# TD8Edaughter.net
KiCad netlist of a schematic drawn in EAGLE
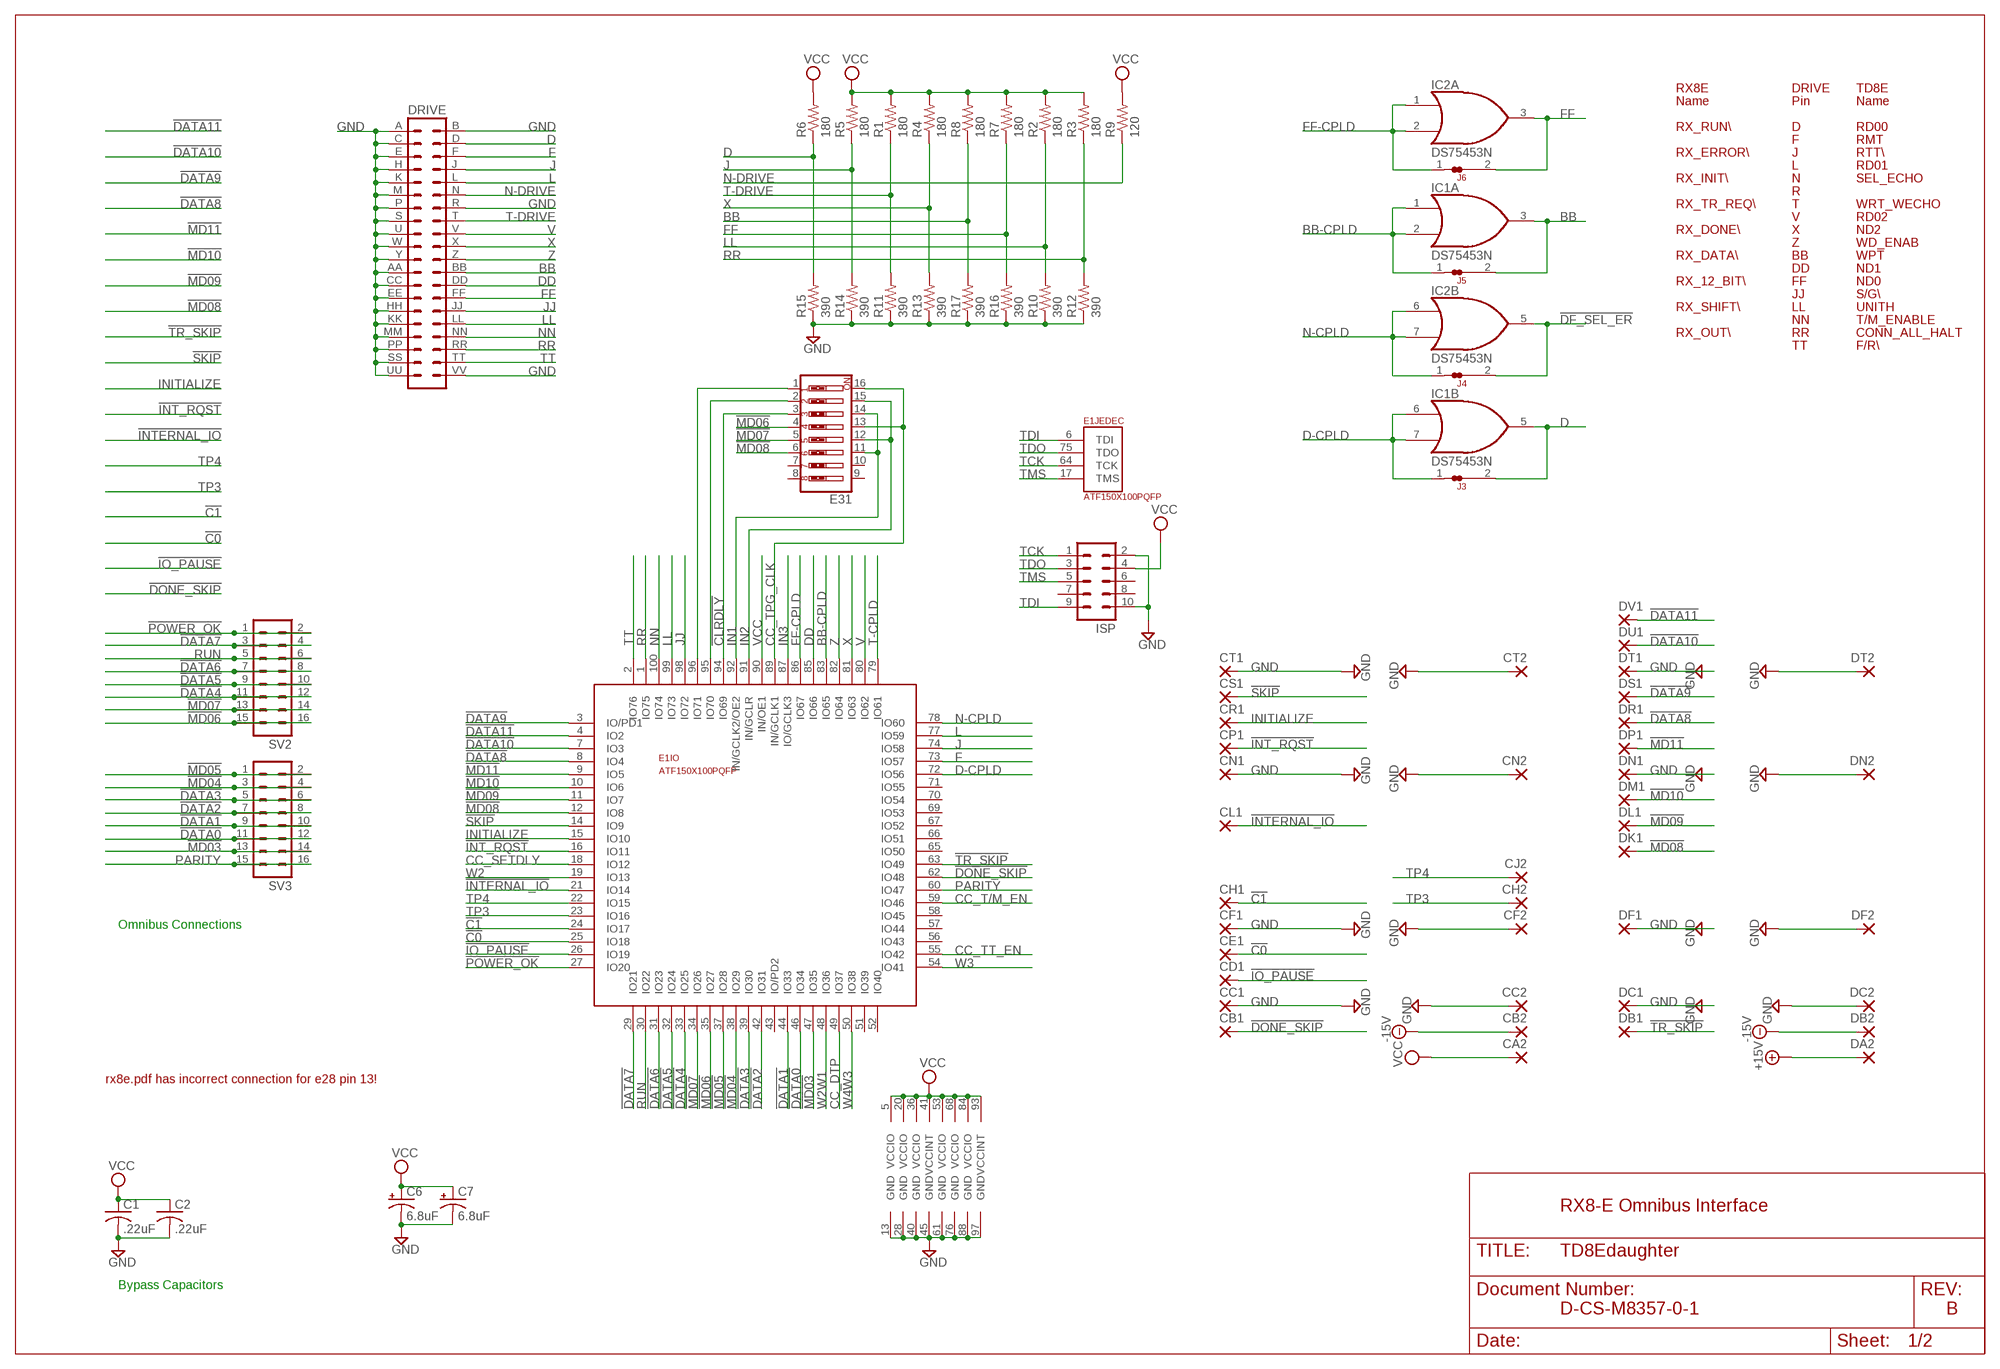
[diagram p0: schematic, sheet 1]
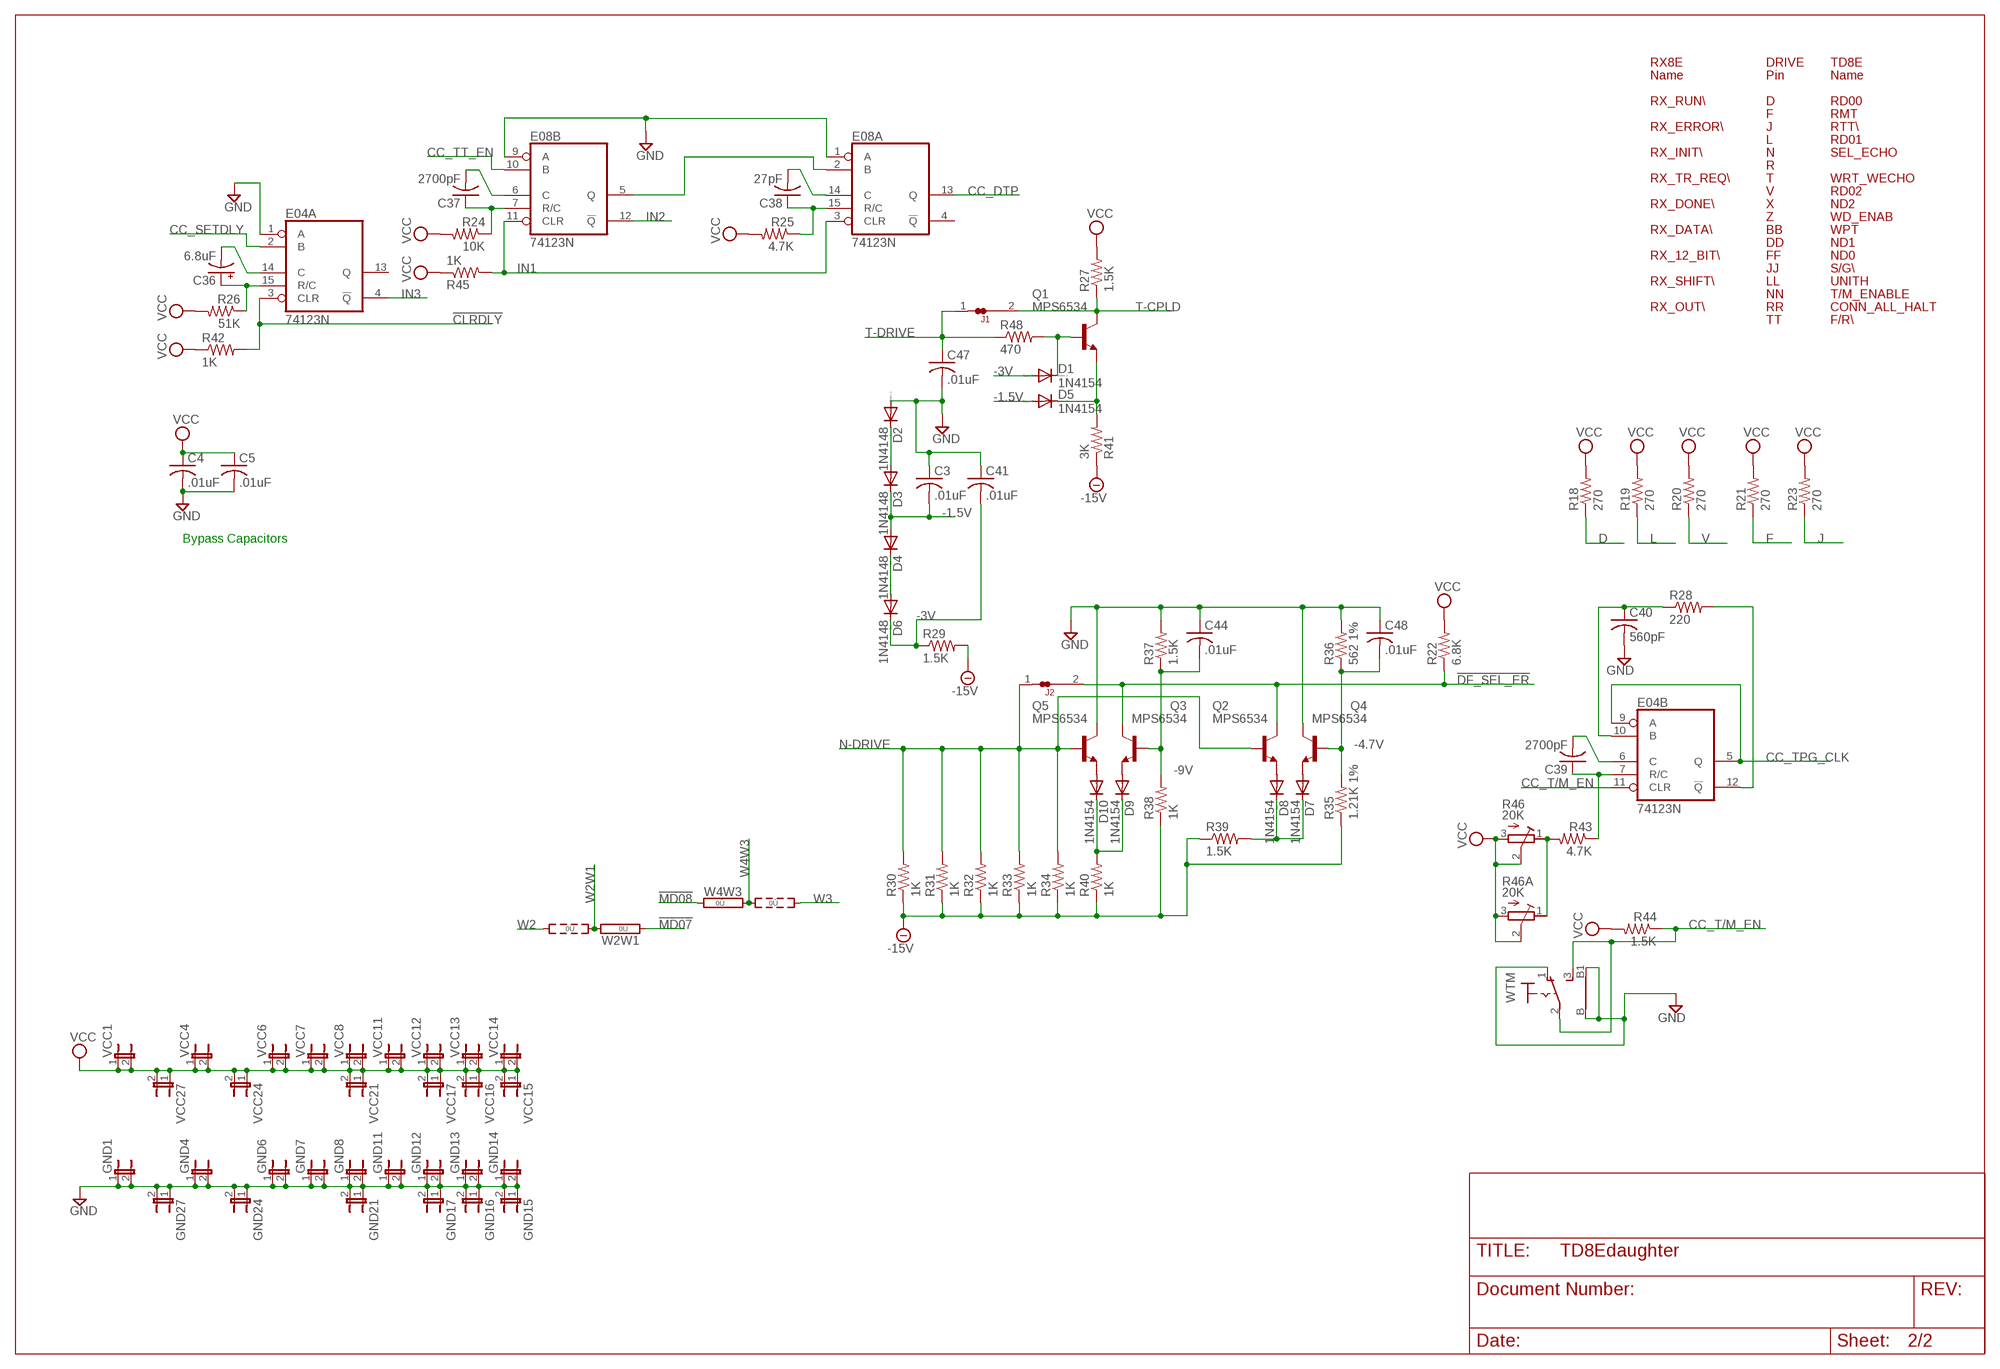
[diagram p1: schematic, sheet 2]

(export (version "E")
  (design (tool "Eeschema 10.0.6"))
  (components
    (comp (ref "C1")
      (value ".22uF")
      (footprint "eagle-import:C050-025X075")
      (libsource (lib "eagle-import") (part "C-US050-025X075"))
    )
    (comp (ref "C2")
      (value ".22uF")
      (footprint "eagle-import:C050-025X075")
      (libsource (lib "eagle-import") (part "C-US050-025X075"))
    )
    (comp (ref "C6")
      (value "6.8uF")
      (footprint "eagle-import:E12-8")
      (libsource (lib "eagle-import") (part "CPOL-USE20-8AXIAL"))
    )
    (comp (ref "C7")
      (value "6.8uF")
      (footprint "eagle-import:E12-8")
      (libsource (lib "eagle-import") (part "CPOL-USE20-8AXIAL"))
    )
    (comp (ref "CA2")
      (value "1,6/0,9")
      (footprint "eagle-import:1,6_0,9")
      (libsource (lib "eagle-import") (part "1,6/0,9"))
    )
    (comp (ref "CB1")
      (value "1,6/0,9")
      (footprint "eagle-import:1,6_0,9")
      (libsource (lib "eagle-import") (part "1,6/0,9"))
    )
    (comp (ref "CB2")
      (value "1,6/0,9")
      (footprint "eagle-import:1,6_0,9")
      (libsource (lib "eagle-import") (part "1,6/0,9"))
    )
    (comp (ref "CC1")
      (value "1,6/0,9")
      (footprint "eagle-import:1,6_0,9")
      (libsource (lib "eagle-import") (part "1,6/0,9"))
    )
    (comp (ref "CC2")
      (value "1,6/0,9")
      (footprint "eagle-import:1,6_0,9")
      (libsource (lib "eagle-import") (part "1,6/0,9"))
    )
    (comp (ref "CD1")
      (value "1,6/0,9")
      (footprint "eagle-import:1,6_0,9")
      (libsource (lib "eagle-import") (part "1,6/0,9"))
    )
    (comp (ref "CE1")
      (value "1,6/0,9")
      (footprint "eagle-import:1,6_0,9")
      (libsource (lib "eagle-import") (part "1,6/0,9"))
    )
    (comp (ref "CF1")
      (value "1,6/0,9")
      (footprint "eagle-import:1,6_0,9")
      (libsource (lib "eagle-import") (part "1,6/0,9"))
    )
    (comp (ref "CF2")
      (value "1,6/0,9")
      (footprint "eagle-import:1,6_0,9")
      (libsource (lib "eagle-import") (part "1,6/0,9"))
    )
    (comp (ref "CH1")
      (value "1,6/0,9")
      (footprint "eagle-import:1,6_0,9")
      (libsource (lib "eagle-import") (part "1,6/0,9"))
    )
    (comp (ref "CH2")
      (value "1,6/0,9")
      (footprint "eagle-import:1,6_0,9")
      (libsource (lib "eagle-import") (part "1,6/0,9"))
    )
    (comp (ref "CJ2")
      (value "1,6/0,9")
      (footprint "eagle-import:1,6_0,9")
      (libsource (lib "eagle-import") (part "1,6/0,9"))
    )
    (comp (ref "CL1")
      (value "1,6/0,9")
      (footprint "eagle-import:1,6_0,9")
      (libsource (lib "eagle-import") (part "1,6/0,9"))
    )
    (comp (ref "CN1")
      (value "1,6/0,9")
      (footprint "eagle-import:1,6_0,9")
      (libsource (lib "eagle-import") (part "1,6/0,9"))
    )
    (comp (ref "CN2")
      (value "1,6/0,9")
      (footprint "eagle-import:1,6_0,9")
      (libsource (lib "eagle-import") (part "1,6/0,9"))
    )
    (comp (ref "CP1")
      (value "1,6/0,9")
      (footprint "eagle-import:1,6_0,9")
      (libsource (lib "eagle-import") (part "1,6/0,9"))
    )
    (comp (ref "CR1")
      (value "1,6/0,9")
      (footprint "eagle-import:1,6_0,9")
      (libsource (lib "eagle-import") (part "1,6/0,9"))
    )
    (comp (ref "CS1")
      (value "1,6/0,9")
      (footprint "eagle-import:1,6_0,9")
      (libsource (lib "eagle-import") (part "1,6/0,9"))
    )
    (comp (ref "CT1")
      (value "1,6/0,9")
      (footprint "eagle-import:1,6_0,9")
      (libsource (lib "eagle-import") (part "1,6/0,9"))
    )
    (comp (ref "CT2")
      (value "1,6/0,9")
      (footprint "eagle-import:1,6_0,9")
      (libsource (lib "eagle-import") (part "1,6/0,9"))
    )
    (comp (ref "DA2")
      (value "1,6/0,9")
      (footprint "eagle-import:1,6_0,9")
      (libsource (lib "eagle-import") (part "1,6/0,9"))
    )
    (comp (ref "DB1")
      (value "1,6/0,9")
      (footprint "eagle-import:1,6_0,9")
      (libsource (lib "eagle-import") (part "1,6/0,9"))
    )
    (comp (ref "DB2")
      (value "1,6/0,9")
      (footprint "eagle-import:1,6_0,9")
      (libsource (lib "eagle-import") (part "1,6/0,9"))
    )
    (comp (ref "DC1")
      (value "1,6/0,9")
      (footprint "eagle-import:1,6_0,9")
      (libsource (lib "eagle-import") (part "1,6/0,9"))
    )
    (comp (ref "DC2")
      (value "1,6/0,9")
      (footprint "eagle-import:1,6_0,9")
      (libsource (lib "eagle-import") (part "1,6/0,9"))
    )
    (comp (ref "DF1")
      (value "1,6/0,9")
      (footprint "eagle-import:1,6_0,9")
      (libsource (lib "eagle-import") (part "1,6/0,9"))
    )
    (comp (ref "DF2")
      (value "1,6/0,9")
      (footprint "eagle-import:1,6_0,9")
      (libsource (lib "eagle-import") (part "1,6/0,9"))
    )
    (comp (ref "DK1")
      (value "1,6/0,9")
      (footprint "eagle-import:1,6_0,9")
      (libsource (lib "eagle-import") (part "1,6/0,9"))
    )
    (comp (ref "DL1")
      (value "1,6/0,9")
      (footprint "eagle-import:1,6_0,9")
      (libsource (lib "eagle-import") (part "1,6/0,9"))
    )
    (comp (ref "DM1")
      (value "1,6/0,9")
      (footprint "eagle-import:1,6_0,9")
      (libsource (lib "eagle-import") (part "1,6/0,9"))
    )
    (comp (ref "DN1")
      (value "1,6/0,9")
      (footprint "eagle-import:1,6_0,9")
      (libsource (lib "eagle-import") (part "1,6/0,9"))
    )
    (comp (ref "DN2")
      (value "1,6/0,9")
      (footprint "eagle-import:1,6_0,9")
      (libsource (lib "eagle-import") (part "1,6/0,9"))
    )
    (comp (ref "DP1")
      (value "1,6/0,9")
      (footprint "eagle-import:1,6_0,9")
      (libsource (lib "eagle-import") (part "1,6/0,9"))
    )
    (comp (ref "DR1")
      (value "1,6/0,9")
      (footprint "eagle-import:1,6_0,9")
      (libsource (lib "eagle-import") (part "1,6/0,9"))
    )
    (comp (ref "DRIVE")
      (value "DEC40PINH")
      (footprint "eagle-import:DEC40PINH")
      (libsource (lib "eagle-import") (part "DEC40PINH"))
    )
    (comp (ref "DS1")
      (value "1,6/0,9")
      (footprint "eagle-import:1,6_0,9")
      (libsource (lib "eagle-import") (part "1,6/0,9"))
    )
    (comp (ref "DT1")
      (value "1,6/0,9")
      (footprint "eagle-import:1,6_0,9")
      (libsource (lib "eagle-import") (part "1,6/0,9"))
    )
    (comp (ref "DT2")
      (value "1,6/0,9")
      (footprint "eagle-import:1,6_0,9")
      (libsource (lib "eagle-import") (part "1,6/0,9"))
    )
    (comp (ref "DU1")
      (value "1,6/0,9")
      (footprint "eagle-import:1,6_0,9")
      (libsource (lib "eagle-import") (part "1,6/0,9"))
    )
    (comp (ref "DV1")
      (value "1,6/0,9")
      (footprint "eagle-import:1,6_0,9")
      (libsource (lib "eagle-import") (part "1,6/0,9"))
    )
    (comp (ref "E1")
      (value "ATF150X100PQFP")
      (footprint "eagle-import:PQFP-100")
      (libsource (lib "eagle-import") (part "ATF150X100PQFP"))
    )
    (comp (ref "E31")
      (value "SW_DIP-8")
      (footprint "eagle-import:EDG-08")
      (libsource (lib "eagle-import") (part "SW_DIP-8"))
    )
    (comp (ref "IC1")
      (value "DS75453N")
      (footprint "eagle-import:DIL08")
      (libsource (lib "eagle-import") (part "DS75453N"))
    )
    (comp (ref "IC2")
      (value "DS75453N")
      (footprint "eagle-import:DIL08")
      (libsource (lib "eagle-import") (part "DS75453N"))
    )
    (comp (ref "ISP")
      (value "ML10")
      (footprint "eagle-import:ML10")
      (libsource (lib "eagle-import") (part "ML10"))
    )
    (comp (ref "J3")
      (value "JUMPER-NC2")
      (footprint "eagle-import:NC2")
      (libsource (lib "eagle-import") (part "JUMPER-NC2"))
    )
    (comp (ref "J4")
      (value "JUMPER-NC2")
      (footprint "eagle-import:NC2")
      (libsource (lib "eagle-import") (part "JUMPER-NC2"))
    )
    (comp (ref "J5")
      (value "JUMPER-NC2")
      (footprint "eagle-import:NC2")
      (libsource (lib "eagle-import") (part "JUMPER-NC2"))
    )
    (comp (ref "J6")
      (value "JUMPER-NC2")
      (footprint "eagle-import:NC2")
      (libsource (lib "eagle-import") (part "JUMPER-NC2"))
    )
    (comp (ref "R1")
      (value "180")
      (footprint "eagle-import:0207_10")
      (libsource (lib "eagle-import") (part "R-US_0207/10"))
    )
    (comp (ref "R2")
      (value "180")
      (footprint "eagle-import:0207_10")
      (libsource (lib "eagle-import") (part "R-US_0207/10"))
    )
    (comp (ref "R3")
      (value "180")
      (footprint "eagle-import:0207_10")
      (libsource (lib "eagle-import") (part "R-US_0207/10"))
    )
    (comp (ref "R4")
      (value "180")
      (footprint "eagle-import:0207_10")
      (libsource (lib "eagle-import") (part "R-US_0207/10"))
    )
    (comp (ref "R5")
      (value "180")
      (footprint "eagle-import:0207_10")
      (libsource (lib "eagle-import") (part "R-US_0207/10"))
    )
    (comp (ref "R6")
      (value "180")
      (footprint "eagle-import:0207_10")
      (libsource (lib "eagle-import") (part "R-US_0207/10"))
    )
    (comp (ref "R7")
      (value "180")
      (footprint "eagle-import:0207_10")
      (libsource (lib "eagle-import") (part "R-US_0207/10"))
    )
    (comp (ref "R8")
      (value "180")
      (footprint "eagle-import:0207_10")
      (libsource (lib "eagle-import") (part "R-US_0207/10"))
    )
    (comp (ref "R9")
      (value "120")
      (footprint "eagle-import:0207_10")
      (libsource (lib "eagle-import") (part "R-US_0207/10"))
    )
    (comp (ref "R10")
      (value "390")
      (footprint "eagle-import:0207_10")
      (libsource (lib "eagle-import") (part "R-US_0207/10"))
    )
    (comp (ref "R11")
      (value "390")
      (footprint "eagle-import:0207_10")
      (libsource (lib "eagle-import") (part "R-US_0207/10"))
    )
    (comp (ref "R12")
      (value "390")
      (footprint "eagle-import:0207_10")
      (libsource (lib "eagle-import") (part "R-US_0207/10"))
    )
    (comp (ref "R13")
      (value "390")
      (footprint "eagle-import:0207_10")
      (libsource (lib "eagle-import") (part "R-US_0207/10"))
    )
    (comp (ref "R14")
      (value "390")
      (footprint "eagle-import:0207_10")
      (libsource (lib "eagle-import") (part "R-US_0207/10"))
    )
    (comp (ref "R15")
      (value "390")
      (footprint "eagle-import:0207_10")
      (libsource (lib "eagle-import") (part "R-US_0207/10"))
    )
    (comp (ref "R16")
      (value "390")
      (footprint "eagle-import:0207_10")
      (libsource (lib "eagle-import") (part "R-US_0207/10"))
    )
    (comp (ref "R17")
      (value "390")
      (footprint "eagle-import:0207_10")
      (libsource (lib "eagle-import") (part "R-US_0207/10"))
    )
    (comp (ref "SV2")
      (value "MA08-2")
      (footprint "eagle-import:MA08-2")
      (libsource (lib "eagle-import") (part "MA08-2"))
    )
    (comp (ref "SV3")
      (value "MA08-2")
      (footprint "eagle-import:MA08-2")
      (libsource (lib "eagle-import") (part "MA08-2"))
    )
    (comp (ref "C3")
      (value ".01uF")
      (footprint "eagle-import:C050-025X075")
      (libsource (lib "eagle-import") (part "C-US050-025X075"))
    )
    (comp (ref "C4")
      (value ".01uF")
      (footprint "eagle-import:C050-025X075")
      (libsource (lib "eagle-import") (part "C-US050-025X075"))
    )
    (comp (ref "C5")
      (value ".01uF")
      (footprint "eagle-import:C050-025X075")
      (libsource (lib "eagle-import") (part "C-US050-025X075"))
    )
    (comp (ref "C36")
      (value "6.8uF")
      (footprint "eagle-import:E12-8")
      (libsource (lib "eagle-import") (part "CPOL-USE20-8AXIAL"))
    )
    (comp (ref "C37")
      (value "2700pF")
      (footprint "eagle-import:C102-043X133")
      (libsource (lib "eagle-import") (part "C-US102-043X133"))
    )
    (comp (ref "C38")
      (value "27pF")
      (footprint "eagle-import:C050-025X075")
      (libsource (lib "eagle-import") (part "C-US050-025X075"))
    )
    (comp (ref "C39")
      (value "2700pF")
      (footprint "eagle-import:C102-043X133")
      (libsource (lib "eagle-import") (part "C-US102-043X133"))
    )
    (comp (ref "C40")
      (value "560pF")
      (footprint "eagle-import:C075-032X103")
      (libsource (lib "eagle-import") (part "C-US075-032X103"))
    )
    (comp (ref "C41")
      (value ".01uF")
      (footprint "eagle-import:C050-025X075")
      (libsource (lib "eagle-import") (part "C-US050-025X075"))
    )
    (comp (ref "C44")
      (value ".01uF")
      (footprint "eagle-import:C050-025X075")
      (libsource (lib "eagle-import") (part "C-US050-025X075"))
    )
    (comp (ref "C47")
      (value ".01uF")
      (footprint "eagle-import:C050-025X075")
      (libsource (lib "eagle-import") (part "C-US050-025X075"))
    )
    (comp (ref "C48")
      (value ".01uF")
      (footprint "eagle-import:C050-025X075")
      (libsource (lib "eagle-import") (part "C-US050-025X075"))
    )
    (comp (ref "D1")
      (value "1N4154")
      (footprint "eagle-import:DO35-10")
      (libsource (lib "eagle-import") (part "1N4148DO35-10"))
    )
    (comp (ref "D2")
      (value "1N4148")
      (footprint "eagle-import:DO35-10")
      (libsource (lib "eagle-import") (part "1N4148DO35-10"))
    )
    (comp (ref "D3")
      (value "1N4148")
      (footprint "eagle-import:DO35-10")
      (libsource (lib "eagle-import") (part "1N4148DO35-10"))
    )
    (comp (ref "D4")
      (value "1N4148")
      (footprint "eagle-import:DO35-10")
      (libsource (lib "eagle-import") (part "1N4148DO35-10"))
    )
    (comp (ref "D5")
      (value "1N4154")
      (footprint "eagle-import:DO35-10")
      (libsource (lib "eagle-import") (part "1N4148DO35-10"))
    )
    (comp (ref "D6")
      (value "1N4148")
      (footprint "eagle-import:DO35-10")
      (libsource (lib "eagle-import") (part "1N4148DO35-10"))
    )
    (comp (ref "D7")
      (value "1N4154")
      (footprint "eagle-import:DO35-10")
      (libsource (lib "eagle-import") (part "1N4148DO35-10"))
    )
    (comp (ref "D8")
      (value "1N4154")
      (footprint "eagle-import:DO35-10")
      (libsource (lib "eagle-import") (part "1N4148DO35-10"))
    )
    (comp (ref "D9")
      (value "1N4154")
      (footprint "eagle-import:DO35-10")
      (libsource (lib "eagle-import") (part "1N4148DO35-10"))
    )
    (comp (ref "D10")
      (value "1N4154")
      (footprint "eagle-import:DO35-10")
      (libsource (lib "eagle-import") (part "1N4148DO35-10"))
    )
    (comp (ref "E04")
      (value "74123N")
      (footprint "eagle-import:DIL16")
      (libsource (lib "eagle-import") (part "74123N"))
    )
    (comp (ref "E08")
      (value "74123N")
      (footprint "eagle-import:DIL16")
      (libsource (lib "eagle-import") (part "74123N"))
    )
    (comp (ref "GND1")
      (value "JP1E")
      (footprint "eagle-import:JP1")
      (libsource (lib "eagle-import") (part "JP1E"))
    )
    (comp (ref "GND4")
      (value "JP1E")
      (footprint "eagle-import:JP1")
      (libsource (lib "eagle-import") (part "JP1E"))
    )
    (comp (ref "GND6")
      (value "JP1E")
      (footprint "eagle-import:JP1")
      (libsource (lib "eagle-import") (part "JP1E"))
    )
    (comp (ref "GND7")
      (value "JP1E")
      (footprint "eagle-import:JP1")
      (libsource (lib "eagle-import") (part "JP1E"))
    )
    (comp (ref "GND8")
      (value "JP1E")
      (footprint "eagle-import:JP1")
      (libsource (lib "eagle-import") (part "JP1E"))
    )
    (comp (ref "GND11")
      (value "JP1E")
      (footprint "eagle-import:JP1")
      (libsource (lib "eagle-import") (part "JP1E"))
    )
    (comp (ref "GND12")
      (value "JP1E")
      (footprint "eagle-import:JP1")
      (libsource (lib "eagle-import") (part "JP1E"))
    )
    (comp (ref "GND13")
      (value "JP1E")
      (footprint "eagle-import:JP1")
      (libsource (lib "eagle-import") (part "JP1E"))
    )
    (comp (ref "GND14")
      (value "JP1E")
      (footprint "eagle-import:JP1")
      (libsource (lib "eagle-import") (part "JP1E"))
    )
    (comp (ref "GND15")
      (value "JP1E")
      (footprint "eagle-import:JP1")
      (libsource (lib "eagle-import") (part "JP1E"))
    )
    (comp (ref "GND16")
      (value "JP1E")
      (footprint "eagle-import:JP1")
      (libsource (lib "eagle-import") (part "JP1E"))
    )
    (comp (ref "GND17")
      (value "JP1E")
      (footprint "eagle-import:JP1")
      (libsource (lib "eagle-import") (part "JP1E"))
    )
    (comp (ref "GND21")
      (value "JP1E")
      (footprint "eagle-import:JP1")
      (libsource (lib "eagle-import") (part "JP1E"))
    )
    (comp (ref "GND24")
      (value "JP1E")
      (footprint "eagle-import:JP1")
      (libsource (lib "eagle-import") (part "JP1E"))
    )
    (comp (ref "GND27")
      (value "JP1E")
      (footprint "eagle-import:JP1")
      (libsource (lib "eagle-import") (part "JP1E"))
    )
    (comp (ref "J1")
      (value "JUMPER-NC")
      (footprint "eagle-import:NC1")
      (libsource (lib "eagle-import") (part "JUMPER-NC1"))
    )
    (comp (ref "J2")
      (value "JUMPER-NC")
      (footprint "eagle-import:NC1")
      (libsource (lib "eagle-import") (part "JUMPER-NC1"))
    )
    (comp (ref "Q1")
      (value "MPS6534")
      (footprint "eagle-import:TO5")
      (libsource (lib "eagle-import") (part "2N2219"))
    )
    (comp (ref "Q2")
      (value "MPS6534")
      (footprint "eagle-import:TO5")
      (libsource (lib "eagle-import") (part "2N2219"))
    )
    (comp (ref "Q3")
      (value "MPS6534")
      (footprint "eagle-import:TO5")
      (libsource (lib "eagle-import") (part "2N2219"))
    )
    (comp (ref "Q4")
      (value "MPS6534")
      (footprint "eagle-import:TO5")
      (libsource (lib "eagle-import") (part "2N2219"))
    )
    (comp (ref "Q5")
      (value "MPS6534")
      (footprint "eagle-import:TO5")
      (libsource (lib "eagle-import") (part "2N2219"))
    )
    (comp (ref "R18")
      (value "270")
      (footprint "eagle-import:0207_10")
      (libsource (lib "eagle-import") (part "R-US_0207/10"))
    )
    (comp (ref "R19")
      (value "270")
      (footprint "eagle-import:0207_10")
      (libsource (lib "eagle-import") (part "R-US_0207/10"))
    )
    (comp (ref "R20")
      (value "270")
      (footprint "eagle-import:0207_10")
      (libsource (lib "eagle-import") (part "R-US_0207/10"))
    )
    (comp (ref "R21")
      (value "270")
      (footprint "eagle-import:0207_10")
      (libsource (lib "eagle-import") (part "R-US_0207/10"))
    )
    (comp (ref "R22")
      (value "6.8K")
      (footprint "eagle-import:0207_10")
      (libsource (lib "eagle-import") (part "R-US_0207/10"))
    )
    (comp (ref "R23")
      (value "270")
      (footprint "eagle-import:0207_10")
      (libsource (lib "eagle-import") (part "R-US_0207/10"))
    )
    (comp (ref "R24")
      (value "10K")
      (footprint "eagle-import:0207_10")
      (libsource (lib "eagle-import") (part "R-US_0207/10"))
    )
    (comp (ref "R25")
      (value "4.7K")
      (footprint "eagle-import:0207_10")
      (libsource (lib "eagle-import") (part "R-US_0207/10"))
    )
    (comp (ref "R26")
      (value "51K")
      (footprint "eagle-import:0207_10")
      (libsource (lib "eagle-import") (part "R-US_0207/10"))
    )
    (comp (ref "R27")
      (value "1.5K")
      (footprint "eagle-import:0207_10")
      (libsource (lib "eagle-import") (part "R-US_0207/10"))
    )
    (comp (ref "R28")
      (value "220")
      (footprint "eagle-import:0207_10")
      (libsource (lib "eagle-import") (part "R-US_0207/10"))
    )
    (comp (ref "R29")
      (value "1.5K")
      (footprint "eagle-import:0207_10")
      (libsource (lib "eagle-import") (part "R-US_0207/10"))
    )
    (comp (ref "R30")
      (value "1K")
      (footprint "eagle-import:0207_10")
      (libsource (lib "eagle-import") (part "R-US_0207/10"))
    )
    (comp (ref "R31")
      (value "1K")
      (footprint "eagle-import:0207_10")
      (libsource (lib "eagle-import") (part "R-US_0207/10"))
    )
    (comp (ref "R32")
      (value "1K")
      (footprint "eagle-import:0207_10")
      (libsource (lib "eagle-import") (part "R-US_0207/10"))
    )
    (comp (ref "R33")
      (value "1K")
      (footprint "eagle-import:0207_10")
      (libsource (lib "eagle-import") (part "R-US_0207/10"))
    )
    (comp (ref "R34")
      (value "1K")
      (footprint "eagle-import:0207_10")
      (libsource (lib "eagle-import") (part "R-US_0207/10"))
    )
    (comp (ref "R35")
      (value "1.21K 1%")
      (footprint "eagle-import:0207_15")
      (libsource (lib "eagle-import") (part "R-US_0207/15"))
    )
    (comp (ref "R36")
      (value "562 1%")
      (footprint "eagle-import:0207_15")
      (libsource (lib "eagle-import") (part "R-US_0207/15"))
    )
    (comp (ref "R37")
      (value "1.5K")
      (footprint "eagle-import:0207_10")
      (libsource (lib "eagle-import") (part "R-US_0207/10"))
    )
    (comp (ref "R38")
      (value "1K")
      (footprint "eagle-import:0207_10")
      (libsource (lib "eagle-import") (part "R-US_0207/10"))
    )
    (comp (ref "R39")
      (value "1.5K")
      (footprint "eagle-import:0207_10")
      (libsource (lib "eagle-import") (part "R-US_0207/10"))
    )
    (comp (ref "R40")
      (value "1K")
      (footprint "eagle-import:0207_10")
      (libsource (lib "eagle-import") (part "R-US_0207/10"))
    )
    (comp (ref "R41")
      (value "3K")
      (footprint "eagle-import:0207_10")
      (libsource (lib "eagle-import") (part "R-US_0207/10"))
    )
    (comp (ref "R42")
      (value "1K")
      (footprint "eagle-import:0207_10")
      (libsource (lib "eagle-import") (part "R-US_0207/10"))
    )
    (comp (ref "R43")
      (value "4.7K")
      (footprint "eagle-import:0207_10")
      (libsource (lib "eagle-import") (part "R-US_0207/10"))
    )
    (comp (ref "R44")
      (value "1.5K")
      (footprint "eagle-import:0207_10")
      (libsource (lib "eagle-import") (part "R-US_0207/10"))
    )
    (comp (ref "R45")
      (value "1K")
      (footprint "eagle-import:0207_10")
      (libsource (lib "eagle-import") (part "R-US_0207/10"))
    )
    (comp (ref "R46")
      (value "20K")
      (footprint "eagle-import:3006Y")
      (libsource (lib "eagle-import") (part "275P"))
    )
    (comp (ref "R46A")
      (value "20K")
      (footprint "eagle-import:RTRIM3006P")
      (libsource (lib "eagle-import") (part "R-TRIMM3006P"))
    )
    (comp (ref "R48")
      (value "470")
      (footprint "eagle-import:0207_10")
      (libsource (lib "eagle-import") (part "R-US_0207/10"))
    )
    (comp (ref "VCC1")
      (value "JP1E")
      (footprint "eagle-import:JP1")
      (libsource (lib "eagle-import") (part "JP1E"))
    )
    (comp (ref "VCC4")
      (value "JP1E")
      (footprint "eagle-import:JP1")
      (libsource (lib "eagle-import") (part "JP1E"))
    )
    (comp (ref "VCC6")
      (value "JP1E")
      (footprint "eagle-import:JP1")
      (libsource (lib "eagle-import") (part "JP1E"))
    )
    (comp (ref "VCC7")
      (value "JP1E")
      (footprint "eagle-import:JP1")
      (libsource (lib "eagle-import") (part "JP1E"))
    )
    (comp (ref "VCC8")
      (value "JP1E")
      (footprint "eagle-import:JP1")
      (libsource (lib "eagle-import") (part "JP1E"))
    )
    (comp (ref "VCC11")
      (value "JP1E")
      (footprint "eagle-import:JP1")
      (libsource (lib "eagle-import") (part "JP1E"))
    )
    (comp (ref "VCC12")
      (value "JP1E")
      (footprint "eagle-import:JP1")
      (libsource (lib "eagle-import") (part "JP1E"))
    )
    (comp (ref "VCC13")
      (value "JP1E")
      (footprint "eagle-import:JP1")
      (libsource (lib "eagle-import") (part "JP1E"))
    )
    (comp (ref "VCC14")
      (value "JP1E")
      (footprint "eagle-import:JP1")
      (libsource (lib "eagle-import") (part "JP1E"))
    )
    (comp (ref "VCC15")
      (value "JP1E")
      (footprint "eagle-import:JP1")
      (libsource (lib "eagle-import") (part "JP1E"))
    )
    (comp (ref "VCC16")
      (value "JP1E")
      (footprint "eagle-import:JP1")
      (libsource (lib "eagle-import") (part "JP1E"))
    )
    (comp (ref "VCC17")
      (value "JP1E")
      (footprint "eagle-import:JP1")
      (libsource (lib "eagle-import") (part "JP1E"))
    )
    (comp (ref "VCC21")
      (value "JP1E")
      (footprint "eagle-import:JP1")
      (libsource (lib "eagle-import") (part "JP1E"))
    )
    (comp (ref "VCC24")
      (value "JP1E")
      (footprint "eagle-import:JP1")
      (libsource (lib "eagle-import") (part "JP1E"))
    )
    (comp (ref "VCC27")
      (value "JP1E")
      (footprint "eagle-import:JP1")
      (libsource (lib "eagle-import") (part "JP1E"))
    )
    (comp (ref "W2W1")
      (value "0R2")
      (footprint "eagle-import:0R2_10")
      (libsource (lib "eagle-import") (part "0R2"))
    )
    (comp (ref "W4W3")
      (value "0R2")
      (footprint "eagle-import:0R2_10")
      (libsource (lib "eagle-import") (part "0R2"))
    )
    (comp (ref "WTM")
      (value "9070-1W")
      (footprint "eagle-import:9070-1W")
      (libsource (lib "eagle-import") (part "9070-1W"))
    )
  )
  (nets
    (net (code "1") (name "+15V") (class "Default")
      (node (ref "DA2") (pin "1") (pinfunction "P_1") (pintype "passive"))
    )
    (net (code "2") (name "-1.5V") (class "Default")
      (node (ref "C3") (pin "2") (pinfunction "2_2") (pintype "passive"))
      (node (ref "D3") (pin "C") (pinfunction "C_C") (pintype "passive"))
      (node (ref "D4") (pin "A") (pinfunction "A_A") (pintype "passive"))
      (node (ref "D5") (pin "A") (pinfunction "A_A") (pintype "passive"))
    )
    (net (code "3") (name "-3V") (class "Default")
      (node (ref "C41") (pin "2") (pinfunction "2_2") (pintype "passive"))
      (node (ref "D1") (pin "A") (pinfunction "A_A") (pintype "passive"))
      (node (ref "D6") (pin "C") (pinfunction "C_C") (pintype "passive"))
      (node (ref "R29") (pin "1") (pinfunction "1_1") (pintype "passive"))
    )
    (net (code "4") (name "-4.7V") (class "Default")
      (node (ref "C48") (pin "2") (pinfunction "2_2") (pintype "passive"))
      (node (ref "Q4") (pin "2") (pinfunction "B_2") (pintype "passive"))
      (node (ref "R35") (pin "2") (pinfunction "2_2") (pintype "passive"))
      (node (ref "R36") (pin "1") (pinfunction "1_1") (pintype "passive"))
    )
    (net (code "5") (name "-9V") (class "Default")
      (node (ref "C44") (pin "2") (pinfunction "2_2") (pintype "passive"))
      (node (ref "Q3") (pin "2") (pinfunction "B_2") (pintype "passive"))
      (node (ref "R37") (pin "1") (pinfunction "1_1") (pintype "passive"))
      (node (ref "R38") (pin "2") (pinfunction "2_2") (pintype "passive"))
    )
    (net (code "6") (name "-15V") (class "Default")
      (node (ref "CB2") (pin "1") (pinfunction "P_1") (pintype "passive"))
      (node (ref "DB2") (pin "1") (pinfunction "P_1") (pintype "passive"))
      (node (ref "R29") (pin "2") (pinfunction "2_2") (pintype "passive"))
      (node (ref "R30") (pin "1") (pinfunction "1_1") (pintype "passive"))
      (node (ref "R31") (pin "1") (pinfunction "1_1") (pintype "passive"))
      (node (ref "R32") (pin "1") (pinfunction "1_1") (pintype "passive"))
      (node (ref "R33") (pin "1") (pinfunction "1_1") (pintype "passive"))
      (node (ref "R34") (pin "1") (pinfunction "1_1") (pintype "passive"))
      (node (ref "R35") (pin "1") (pinfunction "1_1") (pintype "passive"))
      (node (ref "R38") (pin "1") (pinfunction "1_1") (pintype "passive"))
      (node (ref "R39") (pin "1") (pinfunction "1_1") (pintype "passive"))
      (node (ref "R40") (pin "1") (pinfunction "1_1") (pintype "passive"))
      (node (ref "R41") (pin "1") (pinfunction "1_1") (pintype "passive"))
    )
    (net (code "7") (name "BB") (class "Default")
      (node (ref "DRIVE") (pin "BB") (pinfunction "24_BB") (pintype "bidirectional"))
      (node (ref "IC1") (pin "3") (pinfunction "O_3") (pintype "open_collector"))
      (node (ref "J5") (pin "2") (pinfunction "2_2") (pintype "bidirectional"))
      (node (ref "R17") (pin "2") (pinfunction "2_2") (pintype "passive"))
      (node (ref "R8") (pin "1") (pinfunction "1_1") (pintype "passive"))
    )
    (net (code "8") (name "BB-CPLD") (class "Default")
      (node (ref "E1") (pin "83") (pinfunction "IO65_83") (pintype "bidirectional"))
      (node (ref "IC1") (pin "1") (pinfunction "I0_1") (pintype "input"))
      (node (ref "IC1") (pin "2") (pinfunction "I1_2") (pintype "input"))
      (node (ref "J5") (pin "1") (pinfunction "1_1") (pintype "bidirectional"))
    )
    (net (code "9") (name "CC_DTP") (class "Default")
      (node (ref "E08") (pin "13") (pinfunction "Q_13") (pintype "output"))
      (node (ref "E1") (pin "49") (pinfunction "IO37_49") (pintype "bidirectional"))
    )
    (net (code "10") (name "CC_SETDLY") (class "Default")
      (node (ref "E04") (pin "2") (pinfunction "B_2") (pintype "input"))
      (node (ref "E1") (pin "18") (pinfunction "IO12_18") (pintype "bidirectional"))
    )
    (net (code "11") (name "CC_TPG_CLK") (class "Default")
      (node (ref "E04") (pin "5") (pinfunction "Q_5") (pintype "output"))
      (node (ref "E04") (pin "9") (pinfunction "A_9") (pintype "input"))
      (node (ref "E1") (pin "89") (pinfunction "IN/GCLK1_89") (pintype "input"))
      (node (ref "E31") (pin "13") (pinfunction "13_13") (pintype "passive"))
      (node (ref "E31") (pin "16") (pinfunction "16_16") (pintype "passive"))
    )
    (net (code "12") (name "CC_TT_EN") (class "Default")
      (node (ref "E08") (pin "10") (pinfunction "B_10") (pintype "input"))
      (node (ref "E1") (pin "55") (pinfunction "IO42_55") (pintype "bidirectional"))
    )
    (net (code "13") (name "CC_T{slash}M_EN") (class "Default")
      (node (ref "E04") (pin "11") (pinfunction "CLR_11") (pintype "input"))
      (node (ref "E1") (pin "59") (pinfunction "IO46_59") (pintype "bidirectional"))
      (node (ref "R44") (pin "1") (pinfunction "1_1") (pintype "passive"))
      (node (ref "WTM") (pin "2") (pinfunction "P_2") (pintype "passive"))
      (node (ref "WTM") (pin "3") (pinfunction "S_3") (pintype "passive"))
    )
    (net (code "14") (name "D") (class "Default")
      (node (ref "DRIVE") (pin "D") (pinfunction "4_D") (pintype "bidirectional"))
      (node (ref "IC1") (pin "5") (pinfunction "O_5") (pintype "open_collector"))
      (node (ref "J3") (pin "2") (pinfunction "2_2") (pintype "bidirectional"))
      (node (ref "R15") (pin "2") (pinfunction "2_2") (pintype "passive"))
      (node (ref "R18") (pin "1") (pinfunction "1_1") (pintype "passive"))
      (node (ref "R6") (pin "1") (pinfunction "1_1") (pintype "passive"))
    )
    (net (code "15") (name "D-CPLD") (class "Default")
      (node (ref "E1") (pin "72") (pinfunction "IO56_72") (pintype "bidirectional"))
      (node (ref "IC1") (pin "6") (pinfunction "I0_6") (pintype "input"))
      (node (ref "IC1") (pin "7") (pinfunction "I1_7") (pintype "input"))
      (node (ref "J3") (pin "1") (pinfunction "1_1") (pintype "bidirectional"))
    )
    (net (code "16") (name "DD") (class "Default")
      (node (ref "DRIVE") (pin "DD") (pinfunction "26_DD") (pintype "bidirectional"))
      (node (ref "E1") (pin "85") (pinfunction "IO66_85") (pintype "bidirectional"))
    )
    (net (code "17") (name "F") (class "Default")
      (node (ref "DRIVE") (pin "F") (pinfunction "6_F") (pintype "bidirectional"))
      (node (ref "E1") (pin "73") (pinfunction "IO57_73") (pintype "bidirectional"))
      (node (ref "R21") (pin "1") (pinfunction "1_1") (pintype "passive"))
    )
    (net (code "18") (name "FF") (class "Default")
      (node (ref "DRIVE") (pin "FF") (pinfunction "28_FF") (pintype "bidirectional"))
      (node (ref "IC2") (pin "3") (pinfunction "O_3") (pintype "open_collector"))
      (node (ref "J6") (pin "2") (pinfunction "2_2") (pintype "bidirectional"))
      (node (ref "R16") (pin "2") (pinfunction "2_2") (pintype "passive"))
      (node (ref "R7") (pin "1") (pinfunction "1_1") (pintype "passive"))
    )
    (net (code "19") (name "FF-CPLD") (class "Default")
      (node (ref "E1") (pin "86") (pinfunction "IO67_86") (pintype "bidirectional"))
      (node (ref "IC2") (pin "1") (pinfunction "I0_1") (pintype "input"))
      (node (ref "IC2") (pin "2") (pinfunction "I1_2") (pintype "input"))
      (node (ref "J6") (pin "1") (pinfunction "1_1") (pintype "bidirectional"))
    )
    (net (code "20") (name "GND") (class "Default")
      (node (ref "C1") (pin "2") (pinfunction "2_2") (pintype "passive"))
      (node (ref "C2") (pin "2") (pinfunction "2_2") (pintype "passive"))
      (node (ref "C3") (pin "1") (pinfunction "1_1") (pintype "passive"))
      (node (ref "C4") (pin "2") (pinfunction "2_2") (pintype "passive"))
      (node (ref "C40") (pin "2") (pinfunction "2_2") (pintype "passive"))
      (node (ref "C41") (pin "1") (pinfunction "1_1") (pintype "passive"))
      (node (ref "C44") (pin "1") (pinfunction "1_1") (pintype "passive"))
      (node (ref "C47") (pin "2") (pinfunction "2_2") (pintype "passive"))
      (node (ref "C48") (pin "1") (pinfunction "1_1") (pintype "passive"))
      (node (ref "C5") (pin "2") (pinfunction "2_2") (pintype "passive"))
      (node (ref "C6") (pin "-") (pinfunction "-_-") (pintype "passive"))
      (node (ref "C7") (pin "-") (pinfunction "-_-") (pintype "passive"))
      (node (ref "CC1") (pin "1") (pinfunction "P_1") (pintype "passive"))
      (node (ref "CC2") (pin "1") (pinfunction "P_1") (pintype "passive"))
      (node (ref "CF1") (pin "1") (pinfunction "P_1") (pintype "passive"))
      (node (ref "CF2") (pin "1") (pinfunction "P_1") (pintype "passive"))
      (node (ref "CN1") (pin "1") (pinfunction "P_1") (pintype "passive"))
      (node (ref "CN2") (pin "1") (pinfunction "P_1") (pintype "passive"))
      (node (ref "CT1") (pin "1") (pinfunction "P_1") (pintype "passive"))
      (node (ref "CT2") (pin "1") (pinfunction "P_1") (pintype "passive"))
      (node (ref "D2") (pin "A") (pinfunction "A_A") (pintype "passive"))
      (node (ref "DC1") (pin "1") (pinfunction "P_1") (pintype "passive"))
      (node (ref "DC2") (pin "1") (pinfunction "P_1") (pintype "passive"))
      (node (ref "DF1") (pin "1") (pinfunction "P_1") (pintype "passive"))
      (node (ref "DF2") (pin "1") (pinfunction "P_1") (pintype "passive"))
      (node (ref "DN1") (pin "1") (pinfunction "P_1") (pintype "passive"))
      (node (ref "DN2") (pin "1") (pinfunction "P_1") (pintype "passive"))
      (node (ref "DRIVE") (pin "A") (pinfunction "1_A") (pintype "bidirectional"))
      (node (ref "DRIVE") (pin "AA") (pinfunction "23_AA") (pintype "bidirectional"))
      (node (ref "DRIVE") (pin "B") (pinfunction "2_B") (pintype "bidirectional"))
      (node (ref "DRIVE") (pin "C") (pinfunction "3_C") (pintype "bidirectional"))
      (node (ref "DRIVE") (pin "CC") (pinfunction "25_CC") (pintype "bidirectional"))
      (node (ref "DRIVE") (pin "E") (pinfunction "5_E") (pintype "bidirectional"))
      (node (ref "DRIVE") (pin "EE") (pinfunction "27_EE") (pintype "bidirectional"))
      (node (ref "DRIVE") (pin "H") (pinfunction "7_H") (pintype "bidirectional"))
      (node (ref "DRIVE") (pin "HH") (pinfunction "29_HH") (pintype "bidirectional"))
      (node (ref "DRIVE") (pin "K") (pinfunction "9_K") (pintype "bidirectional"))
      (node (ref "DRIVE") (pin "KK") (pinfunction "31_KK") (pintype "bidirectional"))
      (node (ref "DRIVE") (pin "M") (pinfunction "11_M") (pintype "bidirectional"))
      (node (ref "DRIVE") (pin "MM") (pinfunction "33_MM") (pintype "bidirectional"))
      (node (ref "DRIVE") (pin "P") (pinfunction "13_P") (pintype "bidirectional"))
      (node (ref "DRIVE") (pin "PP") (pinfunction "35_PP") (pintype "bidirectional"))
      (node (ref "DRIVE") (pin "R") (pinfunction "14_R") (pintype "bidirectional"))
      (node (ref "DRIVE") (pin "S") (pinfunction "15_S") (pintype "bidirectional"))
      (node (ref "DRIVE") (pin "SS") (pinfunction "37_SS") (pintype "bidirectional"))
      (node (ref "DRIVE") (pin "U") (pinfunction "17_U") (pintype "bidirectional"))
      (node (ref "DRIVE") (pin "UU") (pinfunction "39_UU") (pintype "bidirectional"))
      (node (ref "DRIVE") (pin "VV") (pinfunction "40_VV") (pintype "bidirectional"))
      (node (ref "DRIVE") (pin "W") (pinfunction "19_W") (pintype "bidirectional"))
      (node (ref "DRIVE") (pin "Y") (pinfunction "21_Y") (pintype "bidirectional"))
      (node (ref "DT1") (pin "1") (pinfunction "P_1") (pintype "passive"))
      (node (ref "DT2") (pin "1") (pinfunction "P_1") (pintype "passive"))
      (node (ref "E04") (pin "1") (pinfunction "A_1") (pintype "input"))
      (node (ref "E08") (pin "1") (pinfunction "A_1") (pintype "input"))
      (node (ref "E08") (pin "9") (pinfunction "A_9") (pintype "input"))
      (node (ref "E1") (pin "13") (pinfunction "GND_13") (pintype "power_in"))
      (node (ref "E1") (pin "28") (pinfunction "GND_28") (pintype "power_in"))
      (node (ref "E1") (pin "40") (pinfunction "GND_40") (pintype "power_in"))
      (node (ref "E1") (pin "45") (pinfunction "GND_45") (pintype "power_in"))
      (node (ref "E1") (pin "61") (pinfunction "GND_61") (pintype "power_in"))
      (node (ref "E1") (pin "76") (pinfunction "GND_76") (pintype "power_in"))
      (node (ref "E1") (pin "88") (pinfunction "GND_88") (pintype "power_in"))
      (node (ref "E1") (pin "97") (pinfunction "GND_97") (pintype "power_in"))
      (node (ref "GND1") (pin "1") (pinfunction "1_1") (pintype "passive"))
      (node (ref "GND1") (pin "2") (pinfunction "2_2") (pintype "passive"))
      (node (ref "GND11") (pin "1") (pinfunction "1_1") (pintype "passive"))
      (node (ref "GND11") (pin "2") (pinfunction "2_2") (pintype "passive"))
      (node (ref "GND12") (pin "1") (pinfunction "1_1") (pintype "passive"))
      (node (ref "GND12") (pin "2") (pinfunction "2_2") (pintype "passive"))
      (node (ref "GND13") (pin "1") (pinfunction "1_1") (pintype "passive"))
      (node (ref "GND13") (pin "2") (pinfunction "2_2") (pintype "passive"))
      (node (ref "GND14") (pin "1") (pinfunction "1_1") (pintype "passive"))
      (node (ref "GND14") (pin "2") (pinfunction "2_2") (pintype "passive"))
      (node (ref "GND15") (pin "1") (pinfunction "1_1") (pintype "passive"))
      (node (ref "GND15") (pin "2") (pinfunction "2_2") (pintype "passive"))
      (node (ref "GND16") (pin "1") (pinfunction "1_1") (pintype "passive"))
      (node (ref "GND16") (pin "2") (pinfunction "2_2") (pintype "passive"))
      (node (ref "GND17") (pin "1") (pinfunction "1_1") (pintype "passive"))
      (node (ref "GND17") (pin "2") (pinfunction "2_2") (pintype "passive"))
      (node (ref "GND21") (pin "1") (pinfunction "1_1") (pintype "passive"))
      (node (ref "GND21") (pin "2") (pinfunction "2_2") (pintype "passive"))
      (node (ref "GND24") (pin "1") (pinfunction "1_1") (pintype "passive"))
      (node (ref "GND24") (pin "2") (pinfunction "2_2") (pintype "passive"))
      (node (ref "GND27") (pin "1") (pinfunction "1_1") (pintype "passive"))
      (node (ref "GND27") (pin "2") (pinfunction "2_2") (pintype "passive"))
      (node (ref "GND4") (pin "1") (pinfunction "1_1") (pintype "passive"))
      (node (ref "GND4") (pin "2") (pinfunction "2_2") (pintype "passive"))
      (node (ref "GND6") (pin "1") (pinfunction "1_1") (pintype "passive"))
      (node (ref "GND6") (pin "2") (pinfunction "2_2") (pintype "passive"))
      (node (ref "GND7") (pin "1") (pinfunction "1_1") (pintype "passive"))
      (node (ref "GND7") (pin "2") (pinfunction "2_2") (pintype "passive"))
      (node (ref "GND8") (pin "1") (pinfunction "1_1") (pintype "passive"))
      (node (ref "GND8") (pin "2") (pinfunction "2_2") (pintype "passive"))
      (node (ref "ISP") (pin "10") (pinfunction "10_10") (pintype "passive"))
      (node (ref "ISP") (pin "2") (pinfunction "2_2") (pintype "passive"))
      (node (ref "Q4") (pin "3") (pinfunction "C_3") (pintype "passive"))
      (node (ref "Q5") (pin "3") (pinfunction "C_3") (pintype "passive"))
      (node (ref "R10") (pin "1") (pinfunction "1_1") (pintype "passive"))
      (node (ref "R11") (pin "1") (pinfunction "1_1") (pintype "passive"))
      (node (ref "R12") (pin "1") (pinfunction "1_1") (pintype "passive"))
      (node (ref "R13") (pin "1") (pinfunction "1_1") (pintype "passive"))
      (node (ref "R14") (pin "1") (pinfunction "1_1") (pintype "passive"))
      (node (ref "R15") (pin "1") (pinfunction "1_1") (pintype "passive"))
      (node (ref "R16") (pin "1") (pinfunction "1_1") (pintype "passive"))
      (node (ref "R17") (pin "1") (pinfunction "1_1") (pintype "passive"))
      (node (ref "R36") (pin "2") (pinfunction "2_2") (pintype "passive"))
      (node (ref "R37") (pin "2") (pinfunction "2_2") (pintype "passive"))
      (node (ref "WTM") (pin "1") (pinfunction "O_1") (pintype "passive"))
      (node (ref "WTM") (pin "B") (pinfunction "B_B") (pintype "passive"))
      (node (ref "WTM") (pin "B1") (pinfunction "B1_B1") (pintype "passive"))
    )
    (net (code "21") (name "IN1") (class "Default")
      (node (ref "E08") (pin "11") (pinfunction "CLR_11") (pintype "input"))
      (node (ref "E08") (pin "3") (pinfunction "CLR_3") (pintype "input"))
      (node (ref "E1") (pin "92") (pinfunction "IN/GCLK2/OE2_92") (pintype "input"))
      (node (ref "E31") (pin "11") (pinfunction "11_11") (pintype "passive"))
      (node (ref "E31") (pin "14") (pinfunction "14_14") (pintype "passive"))
      (node (ref "R45") (pin "2") (pinfunction "2_2") (pintype "passive"))
    )
    (net (code "22") (name "IN2") (class "Default")
      (node (ref "E08") (pin "12") (pinfunction "~{Q}_12") (pintype "output"))
      (node (ref "E1") (pin "91") (pinfunction "IN/GCLR_91") (pintype "input"))
      (node (ref "E31") (pin "12") (pinfunction "12_12") (pintype "passive"))
      (node (ref "E31") (pin "15") (pinfunction "15_15") (pintype "passive"))
    )
    (net (code "23") (name "IN3") (class "Default")
      (node (ref "E04") (pin "4") (pinfunction "~{Q}_4") (pintype "output"))
      (node (ref "E1") (pin "87") (pinfunction "IO/GCLK3_87") (pintype "bidirectional"))
    )
    (net (code "24") (name "INITIALIZE") (class "Default")
      (node (ref "CR1") (pin "1") (pinfunction "P_1") (pintype "passive"))
      (node (ref "E1") (pin "15") (pinfunction "IO10_15") (pintype "bidirectional"))
    )
    (net (code "25") (name "J") (class "Default")
      (node (ref "DRIVE") (pin "J") (pinfunction "8_J") (pintype "bidirectional"))
      (node (ref "E1") (pin "74") (pinfunction "IO58_74") (pintype "bidirectional"))
      (node (ref "R14") (pin "2") (pinfunction "2_2") (pintype "passive"))
      (node (ref "R23") (pin "1") (pinfunction "1_1") (pintype "passive"))
      (node (ref "R5") (pin "1") (pinfunction "1_1") (pintype "passive"))
    )
    (net (code "26") (name "JJ") (class "Default")
      (node (ref "DRIVE") (pin "JJ") (pinfunction "30_JJ") (pintype "bidirectional"))
      (node (ref "E1") (pin "98") (pinfunction "IO72_98") (pintype "bidirectional"))
    )
    (net (code "27") (name "L") (class "Default")
      (node (ref "DRIVE") (pin "L") (pinfunction "10_L") (pintype "bidirectional"))
      (node (ref "E1") (pin "77") (pinfunction "IO59_77") (pintype "bidirectional"))
      (node (ref "R19") (pin "1") (pinfunction "1_1") (pintype "passive"))
    )
    (net (code "28") (name "LL") (class "Default")
      (node (ref "DRIVE") (pin "LL") (pinfunction "32_LL") (pintype "bidirectional"))
      (node (ref "E1") (pin "99") (pinfunction "IO73_99") (pintype "bidirectional"))
      (node (ref "R10") (pin "2") (pinfunction "2_2") (pintype "passive"))
      (node (ref "R2") (pin "1") (pinfunction "1_1") (pintype "passive"))
    )
    (net (code "29") (name "N-CPLD") (class "Default")
      (node (ref "E1") (pin "78") (pinfunction "IO60_78") (pintype "bidirectional"))
      (node (ref "IC2") (pin "6") (pinfunction "I0_6") (pintype "input"))
      (node (ref "IC2") (pin "7") (pinfunction "I1_7") (pintype "input"))
      (node (ref "J4") (pin "1") (pinfunction "1_1") (pintype "bidirectional"))
    )
    (net (code "30") (name "N-DRIVE") (class "Default")
      (node (ref "DRIVE") (pin "N") (pinfunction "12_N") (pintype "bidirectional"))
      (node (ref "J2") (pin "1") (pinfunction "1_1") (pintype "bidirectional"))
      (node (ref "Q2") (pin "2") (pinfunction "B_2") (pintype "passive"))
      (node (ref "Q5") (pin "2") (pinfunction "B_2") (pintype "passive"))
      (node (ref "R30") (pin "2") (pinfunction "2_2") (pintype "passive"))
      (node (ref "R31") (pin "2") (pinfunction "2_2") (pintype "passive"))
      (node (ref "R32") (pin "2") (pinfunction "2_2") (pintype "passive"))
      (node (ref "R33") (pin "2") (pinfunction "2_2") (pintype "passive"))
      (node (ref "R34") (pin "2") (pinfunction "2_2") (pintype "passive"))
      (node (ref "R9") (pin "1") (pinfunction "1_1") (pintype "passive"))
    )
    (net (code "31") (name "NN") (class "Default")
      (node (ref "DRIVE") (pin "NN") (pinfunction "34_NN") (pintype "bidirectional"))
      (node (ref "E1") (pin "100") (pinfunction "IO74_100") (pintype "bidirectional"))
    )
    (net (code "32") (name "Net-(D2-PadC)") (class "Default")
      (node (ref "D2") (pin "C") (pinfunction "C_C") (pintype "passive"))
      (node (ref "D3") (pin "A") (pinfunction "A_A") (pintype "passive"))
    )
    (net (code "33") (name "Net-(D4-PadC)") (class "Default")
      (node (ref "D4") (pin "C") (pinfunction "C_C") (pintype "passive"))
      (node (ref "D6") (pin "A") (pinfunction "A_A") (pintype "passive"))
    )
    (net (code "34") (name "Net-(D7-PadC)") (class "Default")
      (node (ref "D7") (pin "C") (pinfunction "C_C") (pintype "passive"))
      (node (ref "D8") (pin "C") (pinfunction "C_C") (pintype "passive"))
      (node (ref "R39") (pin "2") (pinfunction "2_2") (pintype "passive"))
    )
    (net (code "35") (name "Net-(D10-PadC)") (class "Default")
      (node (ref "D10") (pin "C") (pinfunction "C_C") (pintype "passive"))
      (node (ref "D9") (pin "C") (pinfunction "C_C") (pintype "passive"))
      (node (ref "R40") (pin "2") (pinfunction "2_2") (pintype "passive"))
    )
    (net (code "36") (name "Net-(E1Q-IO70)") (class "Default")
      (node (ref "E1") (pin "95") (pinfunction "IO70_95") (pintype "bidirectional"))
      (node (ref "E31") (pin "2") (pinfunction "2_2") (pintype "passive"))
    )
    (net (code "37") (name "Net-(E1Q-IO71)") (class "Default")
      (node (ref "E1") (pin "96") (pinfunction "IO71_96") (pintype "bidirectional"))
      (node (ref "E31") (pin "1") (pinfunction "1_1") (pintype "passive"))
    )
    (net (code "38") (name "Net-(E04A-C)") (class "Default")
      (node (ref "C36") (pin "-") (pinfunction "-_-") (pintype "passive"))
      (node (ref "E04") (pin "14") (pinfunction "C_14") (pintype "input"))
    )
    (net (code "39") (name "Net-(E04A-R{slash}C)") (class "Default")
      (node (ref "C36") (pin "+") (pinfunction "+_+") (pintype "passive"))
      (node (ref "E04") (pin "15") (pinfunction "R/C_15") (pintype "input"))
      (node (ref "R26") (pin "1") (pinfunction "1_1") (pintype "passive"))
    )
    (net (code "40") (name "Net-(E04B-B)") (class "Default")
      (node (ref "C40") (pin "1") (pinfunction "1_1") (pintype "passive"))
      (node (ref "E04") (pin "10") (pinfunction "B_10") (pintype "input"))
      (node (ref "R28") (pin "1") (pinfunction "1_1") (pintype "passive"))
    )
    (net (code "41") (name "Net-(E04B-C)") (class "Default")
      (node (ref "C39") (pin "2") (pinfunction "2_2") (pintype "passive"))
      (node (ref "E04") (pin "6") (pinfunction "C_6") (pintype "input"))
    )
    (net (code "42") (name "Net-(E04B-R{slash}C)") (class "Default")
      (node (ref "C39") (pin "1") (pinfunction "1_1") (pintype "passive"))
      (node (ref "E04") (pin "7") (pinfunction "R/C_7") (pintype "input"))
      (node (ref "R43") (pin "1") (pinfunction "1_1") (pintype "passive"))
    )
    (net (code "43") (name "Net-(E04B-~{Q})") (class "Default")
      (node (ref "E04") (pin "12") (pinfunction "~{Q}_12") (pintype "output"))
      (node (ref "R28") (pin "2") (pinfunction "2_2") (pintype "passive"))
    )
    (net (code "44") (name "Net-(E08A-B)") (class "Default")
      (node (ref "E08") (pin "2") (pinfunction "B_2") (pintype "input"))
      (node (ref "E08") (pin "5") (pinfunction "Q_5") (pintype "output"))
    )
    (net (code "45") (name "Net-(E08A-C)") (class "Default")
      (node (ref "C38") (pin "2") (pinfunction "2_2") (pintype "passive"))
      (node (ref "E08") (pin "14") (pinfunction "C_14") (pintype "input"))
    )
    (net (code "46") (name "Net-(E08A-R{slash}C)") (class "Default")
      (node (ref "C38") (pin "1") (pinfunction "1_1") (pintype "passive"))
      (node (ref "E08") (pin "15") (pinfunction "R/C_15") (pintype "input"))
      (node (ref "R25") (pin "1") (pinfunction "1_1") (pintype "passive"))
    )
    (net (code "47") (name "Net-(E08B-C)") (class "Default")
      (node (ref "C37") (pin "2") (pinfunction "2_2") (pintype "passive"))
      (node (ref "E08") (pin "6") (pinfunction "C_6") (pintype "input"))
    )
    (net (code "48") (name "Net-(E08B-R{slash}C)") (class "Default")
      (node (ref "C37") (pin "1") (pinfunction "1_1") (pintype "passive"))
      (node (ref "E08") (pin "7") (pinfunction "R/C_7") (pintype "input"))
      (node (ref "R24") (pin "1") (pinfunction "1_1") (pintype "passive"))
    )
    (net (code "49") (name "Net-(Q1-B)") (class "Default")
      (node (ref "D1") (pin "C") (pinfunction "C_C") (pintype "passive"))
      (node (ref "Q1") (pin "2") (pinfunction "B_2") (pintype "passive"))
      (node (ref "R48") (pin "2") (pinfunction "2_2") (pintype "passive"))
    )
    (net (code "50") (name "Net-(Q1-E)") (class "Default")
      (node (ref "D5") (pin "C") (pinfunction "C_C") (pintype "passive"))
      (node (ref "Q1") (pin "1") (pinfunction "E_1") (pintype "passive"))
      (node (ref "R41") (pin "2") (pinfunction "2_2") (pintype "passive"))
    )
    (net (code "51") (name "Net-(Q2-E)") (class "Default")
      (node (ref "D8") (pin "A") (pinfunction "A_A") (pintype "passive"))
      (node (ref "Q2") (pin "1") (pinfunction "E_1") (pintype "passive"))
    )
    (net (code "52") (name "Net-(Q3-E)") (class "Default")
      (node (ref "D9") (pin "A") (pinfunction "A_A") (pintype "passive"))
      (node (ref "Q3") (pin "1") (pinfunction "E_1") (pintype "passive"))
    )
    (net (code "53") (name "Net-(Q4-E)") (class "Default")
      (node (ref "D7") (pin "A") (pinfunction "A_A") (pintype "passive"))
      (node (ref "Q4") (pin "1") (pinfunction "E_1") (pintype "passive"))
    )
    (net (code "54") (name "Net-(Q5-E)") (class "Default")
      (node (ref "D10") (pin "A") (pinfunction "A_A") (pintype "passive"))
      (node (ref "Q5") (pin "1") (pinfunction "E_1") (pintype "passive"))
    )
    (net (code "55") (name "Net-(R46-A)") (class "Default")
      (node (ref "R43") (pin "2") (pinfunction "2_2") (pintype "passive"))
      (node (ref "R46") (pin "1") (pinfunction "A_1") (pintype "passive"))
      (node (ref "R46A") (pin "1") (pinfunction "E_1") (pintype "passive"))
    )
    (net (code "56") (name "PARITY") (class "Default")
      (node (ref "E1") (pin "60") (pinfunction "IO47_60") (pintype "bidirectional"))
      (node (ref "SV3") (pin "15") (pinfunction "15_15") (pintype "passive"))
      (node (ref "SV3") (pin "16") (pinfunction "16_16") (pintype "passive"))
    )
    (net (code "57") (name "RR") (class "Default")
      (node (ref "DRIVE") (pin "RR") (pinfunction "36_RR") (pintype "bidirectional"))
      (node (ref "E1") (pin "1") (pinfunction "IO75_1") (pintype "bidirectional"))
      (node (ref "R12") (pin "2") (pinfunction "2_2") (pintype "passive"))
      (node (ref "R3") (pin "1") (pinfunction "1_1") (pintype "passive"))
    )
    (net (code "58") (name "RUN") (class "Default")
      (node (ref "E1") (pin "30") (pinfunction "IO22_30") (pintype "bidirectional"))
      (node (ref "SV2") (pin "5") (pinfunction "5_5") (pintype "passive"))
      (node (ref "SV2") (pin "6") (pinfunction "6_6") (pintype "passive"))
    )
    (net (code "59") (name "T-CPLD") (class "Default")
      (node (ref "E1") (pin "79") (pinfunction "IO61_79") (pintype "bidirectional"))
      (node (ref "J1") (pin "2") (pinfunction "2_2") (pintype "bidirectional"))
      (node (ref "Q1") (pin "3") (pinfunction "C_3") (pintype "passive"))
      (node (ref "R27") (pin "1") (pinfunction "1_1") (pintype "passive"))
    )
    (net (code "60") (name "T-DRIVE") (class "Default")
      (node (ref "C47") (pin "1") (pinfunction "1_1") (pintype "passive"))
      (node (ref "DRIVE") (pin "T") (pinfunction "16_T") (pintype "bidirectional"))
      (node (ref "J1") (pin "1") (pinfunction "1_1") (pintype "bidirectional"))
      (node (ref "R1") (pin "1") (pinfunction "1_1") (pintype "passive"))
      (node (ref "R11") (pin "2") (pinfunction "2_2") (pintype "passive"))
      (node (ref "R48") (pin "1") (pinfunction "1_1") (pintype "passive"))
    )
    (net (code "61") (name "TCK") (class "Default")
      (node (ref "E1") (pin "64") (pinfunction "TCK_64") (pintype "bidirectional"))
      (node (ref "ISP") (pin "1") (pinfunction "1_1") (pintype "passive"))
    )
    (net (code "62") (name "TDI") (class "Default")
      (node (ref "E1") (pin "6") (pinfunction "TDI_6") (pintype "bidirectional"))
      (node (ref "ISP") (pin "9") (pinfunction "9_9") (pintype "passive"))
    )
    (net (code "63") (name "TDO") (class "Default")
      (node (ref "E1") (pin "75") (pinfunction "TDO_75") (pintype "bidirectional"))
      (node (ref "ISP") (pin "3") (pinfunction "3_3") (pintype "passive"))
    )
    (net (code "64") (name "TMS") (class "Default")
      (node (ref "E1") (pin "17") (pinfunction "TMS_17") (pintype "bidirectional"))
      (node (ref "ISP") (pin "5") (pinfunction "5_5") (pintype "passive"))
    )
    (net (code "65") (name "TP3") (class "Default")
      (node (ref "CH2") (pin "1") (pinfunction "P_1") (pintype "passive"))
      (node (ref "E1") (pin "23") (pinfunction "IO16_23") (pintype "bidirectional"))
    )
    (net (code "66") (name "TP4") (class "Default")
      (node (ref "CJ2") (pin "1") (pinfunction "P_1") (pintype "passive"))
      (node (ref "E1") (pin "22") (pinfunction "IO15_22") (pintype "bidirectional"))
    )
    (net (code "67") (name "TT") (class "Default")
      (node (ref "DRIVE") (pin "TT") (pinfunction "38_TT") (pintype "bidirectional"))
      (node (ref "E1") (pin "2") (pinfunction "IO76_2") (pintype "bidirectional"))
    )
    (net (code "68") (name "V") (class "Default")
      (node (ref "DRIVE") (pin "V") (pinfunction "18_V") (pintype "bidirectional"))
      (node (ref "E1") (pin "80") (pinfunction "IO62_80") (pintype "bidirectional"))
      (node (ref "R20") (pin "1") (pinfunction "1_1") (pintype "passive"))
    )
    (net (code "69") (name "VCC") (class "Default")
      (node (ref "C1") (pin "1") (pinfunction "1_1") (pintype "passive"))
      (node (ref "C2") (pin "1") (pinfunction "1_1") (pintype "passive"))
      (node (ref "C4") (pin "1") (pinfunction "1_1") (pintype "passive"))
      (node (ref "C5") (pin "1") (pinfunction "1_1") (pintype "passive"))
      (node (ref "C6") (pin "+") (pinfunction "+_+") (pintype "passive"))
      (node (ref "C7") (pin "+") (pinfunction "+_+") (pintype "passive"))
      (node (ref "CA2") (pin "1") (pinfunction "P_1") (pintype "passive"))
      (node (ref "E1") (pin "20") (pinfunction "VCCIO_20") (pintype "power_in"))
      (node (ref "E1") (pin "36") (pinfunction "VCCIO_36") (pintype "power_in"))
      (node (ref "E1") (pin "41") (pinfunction "VCCINT_41") (pintype "power_in"))
      (node (ref "E1") (pin "5") (pinfunction "VCCIO_5") (pintype "power_in"))
      (node (ref "E1") (pin "53") (pinfunction "VCCIO_53") (pintype "power_in"))
      (node (ref "E1") (pin "68") (pinfunction "VCCIO_68") (pintype "power_in"))
      (node (ref "E1") (pin "84") (pinfunction "VCCIO_84") (pintype "power_in"))
      (node (ref "E1") (pin "90") (pinfunction "IN/OE1_90") (pintype "input"))
      (node (ref "E1") (pin "93") (pinfunction "VCCINT_93") (pintype "power_in"))
      (node (ref "ISP") (pin "4") (pinfunction "4_4") (pintype "passive"))
      (node (ref "R1") (pin "2") (pinfunction "2_2") (pintype "passive"))
      (node (ref "R18") (pin "2") (pinfunction "2_2") (pintype "passive"))
      (node (ref "R19") (pin "2") (pinfunction "2_2") (pintype "passive"))
      (node (ref "R2") (pin "2") (pinfunction "2_2") (pintype "passive"))
      (node (ref "R20") (pin "2") (pinfunction "2_2") (pintype "passive"))
      (node (ref "R21") (pin "2") (pinfunction "2_2") (pintype "passive"))
      (node (ref "R22") (pin "2") (pinfunction "2_2") (pintype "passive"))
      (node (ref "R23") (pin "2") (pinfunction "2_2") (pintype "passive"))
      (node (ref "R24") (pin "2") (pinfunction "2_2") (pintype "passive"))
      (node (ref "R25") (pin "2") (pinfunction "2_2") (pintype "passive"))
      (node (ref "R26") (pin "2") (pinfunction "2_2") (pintype "passive"))
      (node (ref "R27") (pin "2") (pinfunction "2_2") (pintype "passive"))
      (node (ref "R3") (pin "2") (pinfunction "2_2") (pintype "passive"))
      (node (ref "R4") (pin "2") (pinfunction "2_2") (pintype "passive"))
      (node (ref "R42") (pin "1") (pinfunction "1_1") (pintype "passive"))
      (node (ref "R44") (pin "2") (pinfunction "2_2") (pintype "passive"))
      (node (ref "R45") (pin "1") (pinfunction "1_1") (pintype "passive"))
      (node (ref "R46") (pin "2") (pinfunction "S_2") (pintype "passive"))
      (node (ref "R46") (pin "3") (pinfunction "E_3") (pintype "passive"))
      (node (ref "R46A") (pin "2") (pinfunction "S_2") (pintype "passive"))
      (node (ref "R46A") (pin "3") (pinfunction "A_3") (pintype "passive"))
      (node (ref "R5") (pin "2") (pinfunction "2_2") (pintype "passive"))
      (node (ref "R6") (pin "2") (pinfunction "2_2") (pintype "passive"))
      (node (ref "R7") (pin "2") (pinfunction "2_2") (pintype "passive"))
      (node (ref "R8") (pin "2") (pinfunction "2_2") (pintype "passive"))
      (node (ref "R9") (pin "2") (pinfunction "2_2") (pintype "passive"))
      (node (ref "VCC1") (pin "1") (pinfunction "1_1") (pintype "passive"))
      (node (ref "VCC1") (pin "2") (pinfunction "2_2") (pintype "passive"))
      (node (ref "VCC11") (pin "1") (pinfunction "1_1") (pintype "passive"))
      (node (ref "VCC11") (pin "2") (pinfunction "2_2") (pintype "passive"))
      (node (ref "VCC12") (pin "1") (pinfunction "1_1") (pintype "passive"))
      (node (ref "VCC12") (pin "2") (pinfunction "2_2") (pintype "passive"))
      (node (ref "VCC13") (pin "1") (pinfunction "1_1") (pintype "passive"))
      (node (ref "VCC13") (pin "2") (pinfunction "2_2") (pintype "passive"))
      (node (ref "VCC14") (pin "1") (pinfunction "1_1") (pintype "passive"))
      (node (ref "VCC14") (pin "2") (pinfunction "2_2") (pintype "passive"))
      (node (ref "VCC15") (pin "1") (pinfunction "1_1") (pintype "passive"))
      (node (ref "VCC15") (pin "2") (pinfunction "2_2") (pintype "passive"))
      (node (ref "VCC16") (pin "1") (pinfunction "1_1") (pintype "passive"))
      (node (ref "VCC16") (pin "2") (pinfunction "2_2") (pintype "passive"))
      (node (ref "VCC17") (pin "1") (pinfunction "1_1") (pintype "passive"))
      (node (ref "VCC17") (pin "2") (pinfunction "2_2") (pintype "passive"))
      (node (ref "VCC21") (pin "1") (pinfunction "1_1") (pintype "passive"))
      (node (ref "VCC21") (pin "2") (pinfunction "2_2") (pintype "passive"))
      (node (ref "VCC24") (pin "1") (pinfunction "1_1") (pintype "passive"))
      (node (ref "VCC24") (pin "2") (pinfunction "2_2") (pintype "passive"))
      (node (ref "VCC27") (pin "1") (pinfunction "1_1") (pintype "passive"))
      (node (ref "VCC27") (pin "2") (pinfunction "2_2") (pintype "passive"))
      (node (ref "VCC4") (pin "1") (pinfunction "1_1") (pintype "passive"))
      (node (ref "VCC4") (pin "2") (pinfunction "2_2") (pintype "passive"))
      (node (ref "VCC6") (pin "1") (pinfunction "1_1") (pintype "passive"))
      (node (ref "VCC6") (pin "2") (pinfunction "2_2") (pintype "passive"))
      (node (ref "VCC7") (pin "1") (pinfunction "1_1") (pintype "passive"))
      (node (ref "VCC7") (pin "2") (pinfunction "2_2") (pintype "passive"))
      (node (ref "VCC8") (pin "1") (pinfunction "1_1") (pintype "passive"))
      (node (ref "VCC8") (pin "2") (pinfunction "2_2") (pintype "passive"))
    )
    (net (code "70") (name "W2") (class "Default")
      (node (ref "E1") (pin "19") (pinfunction "IO13_19") (pintype "bidirectional"))
      (node (ref "W2W1") (pin "3") (pinfunction "3_3") (pintype "passive"))
    )
    (net (code "71") (name "W2W1") (class "Default")
      (node (ref "E1") (pin "48") (pinfunction "IO36_48") (pintype "bidirectional"))
      (node (ref "W2W1") (pin "2") (pinfunction "2_2") (pintype "passive"))
    )
    (net (code "72") (name "W3") (class "Default")
      (node (ref "E1") (pin "54") (pinfunction "IO41_54") (pintype "bidirectional"))
      (node (ref "W4W3") (pin "3") (pinfunction "3_3") (pintype "passive"))
    )
    (net (code "73") (name "W4W3") (class "Default")
      (node (ref "E1") (pin "50") (pinfunction "IO38_50") (pintype "bidirectional"))
      (node (ref "W4W3") (pin "2") (pinfunction "2_2") (pintype "passive"))
    )
    (net (code "74") (name "X") (class "Default")
      (node (ref "DRIVE") (pin "X") (pinfunction "20_X") (pintype "bidirectional"))
      (node (ref "E1") (pin "81") (pinfunction "IO63_81") (pintype "bidirectional"))
      (node (ref "R13") (pin "2") (pinfunction "2_2") (pintype "passive"))
      (node (ref "R4") (pin "1") (pinfunction "1_1") (pintype "passive"))
    )
    (net (code "75") (name "Z") (class "Default")
      (node (ref "DRIVE") (pin "Z") (pinfunction "22_Z") (pintype "bidirectional"))
      (node (ref "E1") (pin "82") (pinfunction "IO64_82") (pintype "bidirectional"))
    )
    (net (code "76") (name "unconnected-(E1Q-IO39-Pad51)") (class "Default")
      (node (ref "E1") (pin "51") (pinfunction "IO39_51") (pintype "bidirectional"))
    )
    (net (code "77") (name "unconnected-(E1Q-IO40-Pad52)") (class "Default")
      (node (ref "E1") (pin "52") (pinfunction "IO40_52") (pintype "bidirectional"))
    )
    (net (code "78") (name "unconnected-(E1Q-IO43-Pad56)") (class "Default")
      (node (ref "E1") (pin "56") (pinfunction "IO43_56") (pintype "bidirectional"))
    )
    (net (code "79") (name "unconnected-(E1Q-IO44-Pad57)") (class "Default")
      (node (ref "E1") (pin "57") (pinfunction "IO44_57") (pintype "bidirectional"))
    )
    (net (code "80") (name "unconnected-(E1Q-IO45-Pad58)") (class "Default")
      (node (ref "E1") (pin "58") (pinfunction "IO45_58") (pintype "bidirectional"))
    )
    (net (code "81") (name "unconnected-(E1Q-IO50-Pad65)") (class "Default")
      (node (ref "E1") (pin "65") (pinfunction "IO50_65") (pintype "bidirectional"))
    )
    (net (code "82") (name "unconnected-(E1Q-IO51-Pad66)") (class "Default")
      (node (ref "E1") (pin "66") (pinfunction "IO51_66") (pintype "bidirectional"))
    )
    (net (code "83") (name "unconnected-(E1Q-IO52-Pad67)") (class "Default")
      (node (ref "E1") (pin "67") (pinfunction "IO52_67") (pintype "bidirectional"))
    )
    (net (code "84") (name "unconnected-(E1Q-IO53-Pad69)") (class "Default")
      (node (ref "E1") (pin "69") (pinfunction "IO53_69") (pintype "bidirectional"))
    )
    (net (code "85") (name "unconnected-(E1Q-IO54-Pad70)") (class "Default")
      (node (ref "E1") (pin "70") (pinfunction "IO54_70") (pintype "bidirectional"))
    )
    (net (code "86") (name "unconnected-(E1Q-IO55-Pad71)") (class "Default")
      (node (ref "E1") (pin "71") (pinfunction "IO55_71") (pintype "bidirectional"))
    )
    (net (code "87") (name "unconnected-(E1Q-IO{slash}PD2-Pad43)") (class "Default")
      (node (ref "E1") (pin "43") (pinfunction "IO/PD2_43") (pintype "bidirectional"))
    )
    (net (code "88") (name "unconnected-(E04A-Q-Pad13)") (class "Default")
      (node (ref "E04") (pin "13") (pinfunction "Q_13") (pintype "output"))
    )
    (net (code "89") (name "unconnected-(E08A-~{Q}-Pad4)") (class "Default")
      (node (ref "E08") (pin "4") (pinfunction "~{Q}_4") (pintype "output"))
    )
    (net (code "90") (name "unconnected-(E31-Pad7)") (class "Default")
      (node (ref "E31") (pin "7") (pinfunction "7_7") (pintype "passive"))
    )
    (net (code "91") (name "unconnected-(E31-Pad8)") (class "Default")
      (node (ref "E31") (pin "8") (pinfunction "8_8") (pintype "passive"))
    )
    (net (code "92") (name "unconnected-(E31-Pad9)") (class "Default")
      (node (ref "E31") (pin "9") (pinfunction "9_9") (pintype "passive"))
    )
    (net (code "93") (name "unconnected-(E31-Pad10)") (class "Default")
      (node (ref "E31") (pin "10") (pinfunction "10_10") (pintype "passive"))
    )
    (net (code "94") (name "unconnected-(ISP-Pad6)") (class "Default")
      (node (ref "ISP") (pin "6") (pinfunction "6_6") (pintype "passive"))
    )
    (net (code "95") (name "unconnected-(ISP-Pad7)") (class "Default")
      (node (ref "ISP") (pin "7") (pinfunction "7_7") (pintype "passive"))
    )
    (net (code "96") (name "unconnected-(ISP-Pad8)") (class "Default")
      (node (ref "ISP") (pin "8") (pinfunction "8_8") (pintype "passive"))
    )
    (net (code "97") (name "~{C0}") (class "Default")
      (node (ref "CE1") (pin "1") (pinfunction "P_1") (pintype "passive"))
      (node (ref "E1") (pin "25") (pinfunction "IO18_25") (pintype "bidirectional"))
    )
    (net (code "98") (name "~{C1}") (class "Default")
      (node (ref "CH1") (pin "1") (pinfunction "P_1") (pintype "passive"))
      (node (ref "E1") (pin "24") (pinfunction "IO17_24") (pintype "bidirectional"))
    )
    (net (code "99") (name "~{CLRDLY}") (class "Default")
      (node (ref "E04") (pin "3") (pinfunction "CLR_3") (pintype "input"))
      (node (ref "E1") (pin "94") (pinfunction "IO69_94") (pintype "bidirectional"))
      (node (ref "E31") (pin "3") (pinfunction "3_3") (pintype "passive"))
      (node (ref "R42") (pin "2") (pinfunction "2_2") (pintype "passive"))
    )
    (net (code "100") (name "~{DATA0}") (class "Default")
      (node (ref "E1") (pin "46") (pinfunction "IO34_46") (pintype "bidirectional"))
      (node (ref "SV3") (pin "11") (pinfunction "11_11") (pintype "passive"))
      (node (ref "SV3") (pin "12") (pinfunction "12_12") (pintype "passive"))
    )
    (net (code "101") (name "~{DATA1}") (class "Default")
      (node (ref "E1") (pin "44") (pinfunction "IO33_44") (pintype "bidirectional"))
      (node (ref "SV3") (pin "10") (pinfunction "10_10") (pintype "passive"))
      (node (ref "SV3") (pin "9") (pinfunction "9_9") (pintype "passive"))
    )
    (net (code "102") (name "~{DATA2}") (class "Default")
      (node (ref "E1") (pin "42") (pinfunction "IO31_42") (pintype "bidirectional"))
      (node (ref "SV3") (pin "7") (pinfunction "7_7") (pintype "passive"))
      (node (ref "SV3") (pin "8") (pinfunction "8_8") (pintype "passive"))
    )
    (net (code "103") (name "~{DATA3}") (class "Default")
      (node (ref "E1") (pin "39") (pinfunction "IO30_39") (pintype "bidirectional"))
      (node (ref "SV3") (pin "5") (pinfunction "5_5") (pintype "passive"))
      (node (ref "SV3") (pin "6") (pinfunction "6_6") (pintype "passive"))
    )
    (net (code "104") (name "~{DATA4}") (class "Default")
      (node (ref "E1") (pin "33") (pinfunction "IO25_33") (pintype "bidirectional"))
      (node (ref "SV2") (pin "11") (pinfunction "11_11") (pintype "passive"))
      (node (ref "SV2") (pin "12") (pinfunction "12_12") (pintype "passive"))
    )
    (net (code "105") (name "~{DATA5}") (class "Default")
      (node (ref "E1") (pin "32") (pinfunction "IO24_32") (pintype "bidirectional"))
      (node (ref "SV2") (pin "10") (pinfunction "10_10") (pintype "passive"))
      (node (ref "SV2") (pin "9") (pinfunction "9_9") (pintype "passive"))
    )
    (net (code "106") (name "~{DATA6}") (class "Default")
      (node (ref "E1") (pin "31") (pinfunction "IO23_31") (pintype "bidirectional"))
      (node (ref "SV2") (pin "7") (pinfunction "7_7") (pintype "passive"))
      (node (ref "SV2") (pin "8") (pinfunction "8_8") (pintype "passive"))
    )
    (net (code "107") (name "~{DATA7}") (class "Default")
      (node (ref "E1") (pin "29") (pinfunction "IO21_29") (pintype "bidirectional"))
      (node (ref "SV2") (pin "3") (pinfunction "3_3") (pintype "passive"))
      (node (ref "SV2") (pin "4") (pinfunction "4_4") (pintype "passive"))
    )
    (net (code "108") (name "~{DATA8}") (class "Default")
      (node (ref "DR1") (pin "1") (pinfunction "P_1") (pintype "passive"))
      (node (ref "E1") (pin "8") (pinfunction "IO4_8") (pintype "bidirectional"))
    )
    (net (code "109") (name "~{DATA9}") (class "Default")
      (node (ref "DS1") (pin "1") (pinfunction "P_1") (pintype "passive"))
      (node (ref "E1") (pin "3") (pinfunction "IO/PD1_3") (pintype "bidirectional"))
    )
    (net (code "110") (name "~{DATA10}") (class "Default")
      (node (ref "DU1") (pin "1") (pinfunction "P_1") (pintype "passive"))
      (node (ref "E1") (pin "7") (pinfunction "IO3_7") (pintype "bidirectional"))
    )
    (net (code "111") (name "~{DATA11}") (class "Default")
      (node (ref "DV1") (pin "1") (pinfunction "P_1") (pintype "passive"))
      (node (ref "E1") (pin "4") (pinfunction "IO2_4") (pintype "bidirectional"))
    )
    (net (code "112") (name "~{DF_SEL_ER}") (class "Default")
      (node (ref "IC2") (pin "5") (pinfunction "O_5") (pintype "open_collector"))
      (node (ref "J2") (pin "2") (pinfunction "2_2") (pintype "bidirectional"))
      (node (ref "J4") (pin "2") (pinfunction "2_2") (pintype "bidirectional"))
      (node (ref "Q2") (pin "3") (pinfunction "C_3") (pintype "passive"))
      (node (ref "Q3") (pin "3") (pinfunction "C_3") (pintype "passive"))
      (node (ref "R22") (pin "1") (pinfunction "1_1") (pintype "passive"))
    )
    (net (code "113") (name "~{DONE_SKIP}") (class "Default")
      (node (ref "CB1") (pin "1") (pinfunction "P_1") (pintype "passive"))
      (node (ref "E1") (pin "62") (pinfunction "IO48_62") (pintype "bidirectional"))
    )
    (net (code "114") (name "~{INTERNAL_IO}") (class "Default")
      (node (ref "CL1") (pin "1") (pinfunction "P_1") (pintype "passive"))
      (node (ref "E1") (pin "21") (pinfunction "IO14_21") (pintype "bidirectional"))
    )
    (net (code "115") (name "~{INT_RQST}") (class "Default")
      (node (ref "CP1") (pin "1") (pinfunction "P_1") (pintype "passive"))
      (node (ref "E1") (pin "16") (pinfunction "IO11_16") (pintype "bidirectional"))
    )
    (net (code "116") (name "~{IO_PAUSE}") (class "Default")
      (node (ref "CD1") (pin "1") (pinfunction "P_1") (pintype "passive"))
      (node (ref "E1") (pin "26") (pinfunction "IO19_26") (pintype "bidirectional"))
    )
    (net (code "117") (name "~{MD03}") (class "Default")
      (node (ref "E1") (pin "47") (pinfunction "IO35_47") (pintype "bidirectional"))
      (node (ref "SV3") (pin "13") (pinfunction "13_13") (pintype "passive"))
      (node (ref "SV3") (pin "14") (pinfunction "14_14") (pintype "passive"))
    )
    (net (code "118") (name "~{MD04}") (class "Default")
      (node (ref "E1") (pin "38") (pinfunction "IO29_38") (pintype "bidirectional"))
      (node (ref "SV3") (pin "3") (pinfunction "3_3") (pintype "passive"))
      (node (ref "SV3") (pin "4") (pinfunction "4_4") (pintype "passive"))
    )
    (net (code "119") (name "~{MD05}") (class "Default")
      (node (ref "E1") (pin "37") (pinfunction "IO28_37") (pintype "bidirectional"))
      (node (ref "SV3") (pin "1") (pinfunction "1_1") (pintype "passive"))
      (node (ref "SV3") (pin "2") (pinfunction "2_2") (pintype "passive"))
    )
    (net (code "120") (name "~{MD06}") (class "Default")
      (node (ref "E1") (pin "35") (pinfunction "IO27_35") (pintype "bidirectional"))
      (node (ref "E31") (pin "4") (pinfunction "4_4") (pintype "passive"))
      (node (ref "SV2") (pin "15") (pinfunction "15_15") (pintype "passive"))
      (node (ref "SV2") (pin "16") (pinfunction "16_16") (pintype "passive"))
    )
    (net (code "121") (name "~{MD07}") (class "Default")
      (node (ref "E1") (pin "34") (pinfunction "IO26_34") (pintype "bidirectional"))
      (node (ref "E31") (pin "5") (pinfunction "5_5") (pintype "passive"))
      (node (ref "SV2") (pin "13") (pinfunction "13_13") (pintype "passive"))
      (node (ref "SV2") (pin "14") (pinfunction "14_14") (pintype "passive"))
      (node (ref "W2W1") (pin "1") (pinfunction "1_1") (pintype "passive"))
    )
    (net (code "122") (name "~{MD08}") (class "Default")
      (node (ref "DK1") (pin "1") (pinfunction "P_1") (pintype "passive"))
      (node (ref "E1") (pin "12") (pinfunction "IO8_12") (pintype "bidirectional"))
      (node (ref "E31") (pin "6") (pinfunction "6_6") (pintype "passive"))
      (node (ref "W4W3") (pin "1") (pinfunction "1_1") (pintype "passive"))
    )
    (net (code "123") (name "~{MD09}") (class "Default")
      (node (ref "DL1") (pin "1") (pinfunction "P_1") (pintype "passive"))
      (node (ref "E1") (pin "11") (pinfunction "IO7_11") (pintype "bidirectional"))
    )
    (net (code "124") (name "~{MD10}") (class "Default")
      (node (ref "DM1") (pin "1") (pinfunction "P_1") (pintype "passive"))
      (node (ref "E1") (pin "10") (pinfunction "IO6_10") (pintype "bidirectional"))
    )
    (net (code "125") (name "~{MD11}") (class "Default")
      (node (ref "DP1") (pin "1") (pinfunction "P_1") (pintype "passive"))
      (node (ref "E1") (pin "9") (pinfunction "IO5_9") (pintype "bidirectional"))
    )
    (net (code "126") (name "~{POWER_OK}") (class "Default")
      (node (ref "E1") (pin "27") (pinfunction "IO20_27") (pintype "bidirectional"))
      (node (ref "SV2") (pin "1") (pinfunction "1_1") (pintype "passive"))
      (node (ref "SV2") (pin "2") (pinfunction "2_2") (pintype "passive"))
    )
    (net (code "127") (name "~{SKIP}") (class "Default")
      (node (ref "CS1") (pin "1") (pinfunction "P_1") (pintype "passive"))
      (node (ref "E1") (pin "14") (pinfunction "IO9_14") (pintype "bidirectional"))
    )
    (net (code "128") (name "~{TR_SKIP}") (class "Default")
      (node (ref "DB1") (pin "1") (pinfunction "P_1") (pintype "passive"))
      (node (ref "E1") (pin "63") (pinfunction "IO49_63") (pintype "bidirectional"))
    )
  )
)
